# main_sch.net
KiCad netlist of a schematic drawn in Altium Designer
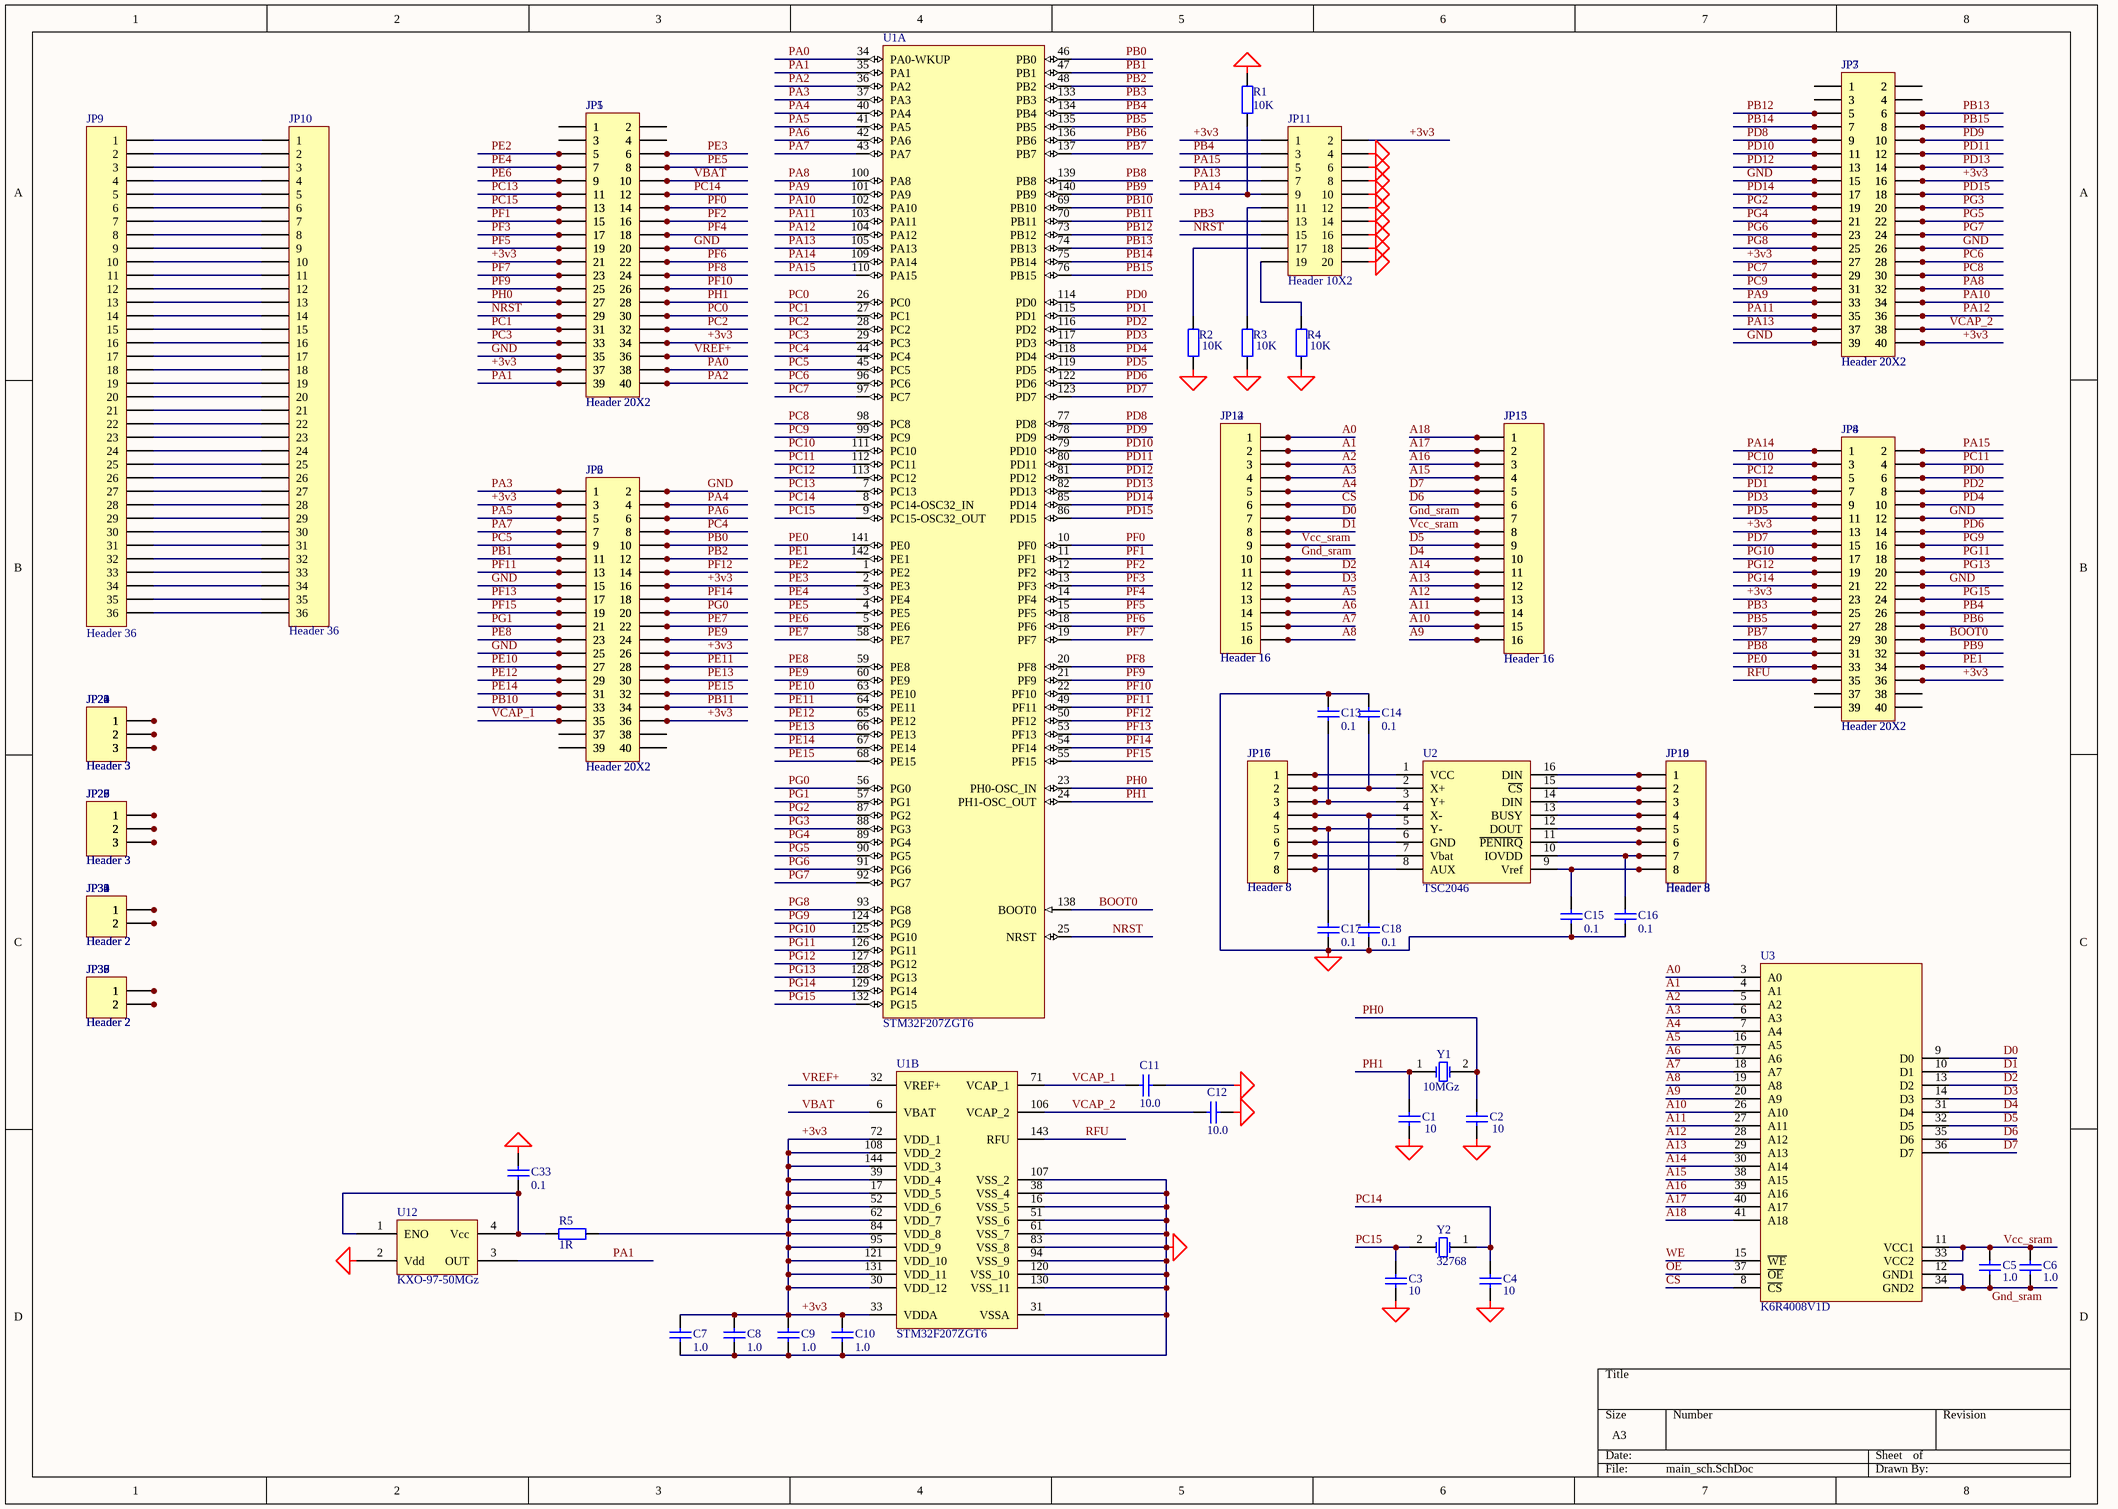
[diagram p0: main_sch.SchDoc]

(export (version "E")
  (design (tool "Eeschema 10.0.6"))
  (components
    (comp (ref "C1")
      (value "10")
      (footprint "_1206")
      (description "Capacitor")
      (fields (field (name "MANUFACTURER") "Generic Components") (field (name "PUBLISHER") "Altium Limited"))
      (libsource (lib "Miscellaneous Devices") (part "Cap Semi"))
    )
    (comp (ref "C2")
      (value "10")
      (footprint "_1206")
      (description "Capacitor")
      (fields (field (name "MANUFACTURER") "Generic Components") (field (name "PUBLISHER") "Altium Limited"))
      (libsource (lib "Miscellaneous Devices") (part "Cap Semi"))
    )
    (comp (ref "C3")
      (value "10")
      (footprint "_1206")
      (description "Capacitor")
      (fields (field (name "MANUFACTURER") "Generic Components") (field (name "PUBLISHER") "Altium Limited"))
      (libsource (lib "Miscellaneous Devices") (part "Cap Semi"))
    )
    (comp (ref "C4")
      (value "10")
      (footprint "_1206")
      (description "Capacitor")
      (fields (field (name "MANUFACTURER") "Generic Components") (field (name "PUBLISHER") "Altium Limited"))
      (libsource (lib "Miscellaneous Devices") (part "Cap Semi"))
    )
    (comp (ref "C5")
      (value "1.0")
      (footprint "_1206")
      (description "Capacitor")
      (fields (field (name "MANUFACTURER") "Generic Components") (field (name "PUBLISHER") "Altium Limited"))
      (libsource (lib "Miscellaneous Devices") (part "Cap Semi"))
    )
    (comp (ref "C6")
      (value "1.0")
      (footprint "_1206")
      (description "Capacitor")
      (fields (field (name "MANUFACTURER") "Generic Components") (field (name "PUBLISHER") "Altium Limited"))
      (libsource (lib "Miscellaneous Devices") (part "Cap Semi"))
    )
    (comp (ref "C7")
      (value "1.0")
      (footprint "_1206")
      (description "Capacitor")
      (fields (field (name "MANUFACTURER") "Generic Components") (field (name "PUBLISHER") "Altium Limited"))
      (libsource (lib "Miscellaneous Devices") (part "Cap Semi"))
    )
    (comp (ref "C8")
      (value "1.0")
      (footprint "_1206")
      (description "Capacitor")
      (fields (field (name "MANUFACTURER") "Generic Components") (field (name "PUBLISHER") "Altium Limited"))
      (libsource (lib "Miscellaneous Devices") (part "Cap Semi"))
    )
    (comp (ref "C9")
      (value "1.0")
      (footprint "_1206")
      (description "Capacitor")
      (fields (field (name "MANUFACTURER") "Generic Components") (field (name "PUBLISHER") "Altium Limited"))
      (libsource (lib "Miscellaneous Devices") (part "Cap Semi"))
    )
    (comp (ref "C10")
      (value "1.0")
      (footprint "_1206")
      (description "Capacitor")
      (fields (field (name "MANUFACTURER") "Generic Components") (field (name "PUBLISHER") "Altium Limited"))
      (libsource (lib "Miscellaneous Devices") (part "Cap Semi"))
    )
    (comp (ref "C11")
      (value "10.0")
      (footprint "_1206")
      (description "Capacitor")
      (fields (field (name "MANUFACTURER") "Generic Components") (field (name "PUBLISHER") "Altium Limited"))
      (libsource (lib "") (part "Cap Semi_1"))
    )
    (comp (ref "C12")
      (value "10.0")
      (footprint "_1206")
      (description "Capacitor")
      (fields (field (name "MANUFACTURER") "Generic Components") (field (name "PUBLISHER") "Altium Limited"))
      (libsource (lib "") (part "Cap Semi_1"))
    )
    (comp (ref "C13")
      (value "0.1")
      (footprint "_1206")
      (description "Capacitor")
      (fields (field (name "MANUFACTURER") "Generic Components") (field (name "PUBLISHER") "Altium Limited"))
      (libsource (lib "Miscellaneous Devices") (part "Cap Semi"))
    )
    (comp (ref "C14")
      (value "0.1")
      (footprint "_1206")
      (description "Capacitor")
      (fields (field (name "MANUFACTURER") "Generic Components") (field (name "PUBLISHER") "Altium Limited"))
      (libsource (lib "Miscellaneous Devices") (part "Cap Semi"))
    )
    (comp (ref "C15")
      (value "0.1")
      (footprint "_1206")
      (description "Capacitor")
      (fields (field (name "MANUFACTURER") "Generic Components") (field (name "PUBLISHER") "Altium Limited"))
      (libsource (lib "Miscellaneous Devices") (part "Cap Semi"))
    )
    (comp (ref "C16")
      (value "0.1")
      (footprint "_1206")
      (description "Capacitor")
      (fields (field (name "MANUFACTURER") "Generic Components") (field (name "PUBLISHER") "Altium Limited"))
      (libsource (lib "Miscellaneous Devices") (part "Cap Semi"))
    )
    (comp (ref "C17")
      (value "0.1")
      (footprint "_1206")
      (description "Capacitor")
      (fields (field (name "MANUFACTURER") "Generic Components") (field (name "PUBLISHER") "Altium Limited"))
      (libsource (lib "Miscellaneous Devices") (part "Cap Semi"))
    )
    (comp (ref "C18")
      (value "0.1")
      (footprint "_1206")
      (description "Capacitor")
      (fields (field (name "MANUFACTURER") "Generic Components") (field (name "PUBLISHER") "Altium Limited"))
      (libsource (lib "Miscellaneous Devices") (part "Cap Semi"))
    )
    (comp (ref "C33")
      (value "0.1")
      (footprint "_1206")
      (description "Capacitor (Semiconductor SIM Model)")
      (fields (field (name "MANUFACTURER") "Generic Components") (field (name "PUBLISHER") "Altium Limited"))
      (libsource (lib "Miscellaneous Devices") (part "Cap Semi"))
    )
    (comp (ref "JP1")
      (value "Header 20X2")
      (footprint "HDR2X20")
      (description "Header, 20-Pin, Dual row")
      (fields (field (name "MANUFACTURER") "Generic Components") (field (name "PUBLISHER") "Altium Limited"))
      (libsource (lib "Miscellaneous Connectors") (part "Header 20X2"))
    )
    (comp (ref "JP2")
      (value "Header 20X2")
      (footprint "HDR2X20")
      (description "Header, 20-Pin, Dual row")
      (fields (field (name "MANUFACTURER") "Generic Components") (field (name "PUBLISHER") "Altium Limited"))
      (libsource (lib "Miscellaneous Connectors") (part "Header 20X2"))
    )
    (comp (ref "JP3")
      (value "Header 20X2")
      (footprint "HDR2X20")
      (description "Header, 20-Pin, Dual row")
      (fields (field (name "MANUFACTURER") "Generic Components") (field (name "PUBLISHER") "Altium Limited"))
      (libsource (lib "Miscellaneous Connectors") (part "Header 20X2"))
    )
    (comp (ref "JP4")
      (value "Header 20X2")
      (footprint "HDR2X20")
      (description "Header, 20-Pin, Dual row")
      (fields (field (name "MANUFACTURER") "Generic Components") (field (name "PUBLISHER") "Altium Limited"))
      (libsource (lib "Miscellaneous Connectors") (part "Header 20X2"))
    )
    (comp (ref "JP5")
      (value "Header 20X2")
      (footprint "HDR2X20")
      (description "Header, 20-Pin, Dual row")
      (fields (field (name "MANUFACTURER") "Generic Components") (field (name "PUBLISHER") "Altium Limited"))
      (libsource (lib "Miscellaneous Connectors") (part "Header 20X2"))
    )
    (comp (ref "JP6")
      (value "Header 20X2")
      (footprint "HDR2X20")
      (description "Header, 20-Pin, Dual row")
      (fields (field (name "MANUFACTURER") "Generic Components") (field (name "PUBLISHER") "Altium Limited"))
      (libsource (lib "Miscellaneous Connectors") (part "Header 20X2"))
    )
    (comp (ref "JP7")
      (value "Header 20X2")
      (footprint "HDR2X20")
      (description "Header, 20-Pin, Dual row")
      (fields (field (name "MANUFACTURER") "Generic Components") (field (name "PUBLISHER") "Altium Limited"))
      (libsource (lib "Miscellaneous Connectors") (part "Header 20X2"))
    )
    (comp (ref "JP8")
      (value "Header 20X2")
      (footprint "HDR2X20")
      (description "Header, 20-Pin, Dual row")
      (fields (field (name "MANUFACTURER") "Generic Components") (field (name "PUBLISHER") "Altium Limited"))
      (libsource (lib "Miscellaneous Connectors") (part "Header 20X2"))
    )
    (comp (ref "JP9")
      (value "Header 36")
      (footprint "3-1734592-6")
      (description "Header, 36-Pin")
      (fields (field (name "MANUFACTURER") "Generic Components") (field (name "PUBLISHER") "Altium Limited"))
      (libsource (lib "") (part "Header 36_1"))
    )
    (comp (ref "JP10")
      (value "Header 36")
      (footprint "HDR2X18")
      (description "Header, 36-Pin")
      (fields (field (name "MANUFACTURER") "Generic Components") (field (name "PUBLISHER") "Altium Limited"))
      (libsource (lib "PAL") (part "Header 36"))
    )
    (comp (ref "JP11")
      (value "Header 10X2")
      (footprint "HDR2X10")
      (description "Header, 10-Pin, Dual row")
      (fields (field (name "MANUFACTURER") "Generic Components") (field (name "PUBLISHER") "Altium Limited"))
      (libsource (lib "Miscellaneous Connectors") (part "Header 10X2"))
    )
    (comp (ref "JP12")
      (value "Header 16")
      (footprint "HDR2X8")
      (description "Header, 16-Pin")
      (fields (field (name "MANUFACTURER") "Generic Components") (field (name "PUBLISHER") "Altium Limited"))
      (libsource (lib "") (part "Header 16_1"))
    )
    (comp (ref "JP13")
      (value "Header 16")
      (footprint "HDR2X8")
      (description "Header, 16-Pin")
      (fields (field (name "MANUFACTURER") "Generic Components") (field (name "PUBLISHER") "Altium Limited"))
      (libsource (lib "Miscellaneous Connectors") (part "Header 16"))
    )
    (comp (ref "JP14")
      (value "Header 16")
      (footprint "HDR2X8")
      (description "Header, 16-Pin")
      (fields (field (name "MANUFACTURER") "Generic Components") (field (name "PUBLISHER") "Altium Limited"))
      (libsource (lib "") (part "Header 16_1"))
    )
    (comp (ref "JP15")
      (value "Header 16")
      (footprint "HDR2X8")
      (description "Header, 16-Pin")
      (fields (field (name "MANUFACTURER") "Generic Components") (field (name "PUBLISHER") "Altium Limited"))
      (libsource (lib "Miscellaneous Connectors") (part "Header 16"))
    )
    (comp (ref "JP16")
      (value "Header 8")
      (footprint "HDR1X8")
      (description "Header, 8-Pin")
      (fields (field (name "MANUFACTURER") "Generic Components") (field (name "PUBLISHER") "Altium Limited"))
      (libsource (lib "") (part "Header 8_1"))
    )
    (comp (ref "JP17")
      (value "Header 8")
      (footprint "HDR1X8")
      (description "Header, 8-Pin")
      (fields (field (name "MANUFACTURER") "Generic Components") (field (name "PUBLISHER") "Altium Limited"))
      (libsource (lib "") (part "Header 8_1"))
    )
    (comp (ref "JP18")
      (value "Header 8")
      (footprint "HDR1X8")
      (description "Header, 8-Pin")
      (fields (field (name "MANUFACTURER") "Generic Components") (field (name "PUBLISHER") "Altium Limited"))
      (libsource (lib "Miscellaneous Connectors") (part "Header 8"))
    )
    (comp (ref "JP19")
      (value "Header 8")
      (footprint "HDR1X8")
      (description "Header, 8-Pin")
      (fields (field (name "MANUFACTURER") "Generic Components") (field (name "PUBLISHER") "Altium Limited"))
      (libsource (lib "Miscellaneous Connectors") (part "Header 8"))
    )
    (comp (ref "JP20")
      (value "Header 3")
      (footprint "HDR1X3")
      (description "Header, 3-Pin")
      (fields (field (name "MANUFACTURER") "Generic Components") (field (name "PUBLISHER") "Altium Limited"))
      (libsource (lib "Miscellaneous Connectors") (part "Header 3"))
    )
    (comp (ref "JP21")
      (value "Header 3")
      (footprint "HDR1X3")
      (description "Header, 3-Pin")
      (fields (field (name "MANUFACTURER") "Generic Components") (field (name "PUBLISHER") "Altium Limited"))
      (libsource (lib "Miscellaneous Connectors") (part "Header 3"))
    )
    (comp (ref "JP22")
      (value "Header 3")
      (footprint "HDR1X3")
      (description "Header, 3-Pin")
      (fields (field (name "MANUFACTURER") "Generic Components") (field (name "PUBLISHER") "Altium Limited"))
      (libsource (lib "Miscellaneous Connectors") (part "Header 3"))
    )
    (comp (ref "JP23")
      (value "Header 3")
      (footprint "HDR1X3")
      (description "Header, 3-Pin")
      (fields (field (name "MANUFACTURER") "Generic Components") (field (name "PUBLISHER") "Altium Limited"))
      (libsource (lib "Miscellaneous Connectors") (part "Header 3"))
    )
    (comp (ref "JP24")
      (value "Header 3")
      (footprint "HDR1X3")
      (description "Header, 3-Pin")
      (fields (field (name "MANUFACTURER") "Generic Components") (field (name "PUBLISHER") "Altium Limited"))
      (libsource (lib "Miscellaneous Connectors") (part "Header 3"))
    )
    (comp (ref "JP25")
      (value "Header 3")
      (footprint "HDR1X3")
      (description "Header, 3-Pin")
      (fields (field (name "MANUFACTURER") "Generic Components") (field (name "PUBLISHER") "Altium Limited"))
      (libsource (lib "Miscellaneous Connectors") (part "Header 3"))
    )
    (comp (ref "JP26")
      (value "Header 3")
      (footprint "HDR1X3")
      (description "Header, 3-Pin")
      (fields (field (name "MANUFACTURER") "Generic Components") (field (name "PUBLISHER") "Altium Limited"))
      (libsource (lib "Miscellaneous Connectors") (part "Header 3"))
    )
    (comp (ref "JP27")
      (value "Header 3")
      (footprint "HDR1X3")
      (description "Header, 3-Pin")
      (fields (field (name "MANUFACTURER") "Generic Components") (field (name "PUBLISHER") "Altium Limited"))
      (libsource (lib "Miscellaneous Connectors") (part "Header 3"))
    )
    (comp (ref "JP28")
      (value "Header 3")
      (footprint "HDR1X3")
      (description "Header, 3-Pin")
      (fields (field (name "MANUFACTURER") "Generic Components") (field (name "PUBLISHER") "Altium Limited"))
      (libsource (lib "Miscellaneous Connectors") (part "Header 3"))
    )
    (comp (ref "JP29")
      (value "Header 3")
      (footprint "HDR1X3")
      (description "Header, 3-Pin")
      (fields (field (name "MANUFACTURER") "Generic Components") (field (name "PUBLISHER") "Altium Limited"))
      (libsource (lib "Miscellaneous Connectors") (part "Header 3"))
    )
    (comp (ref "JP30")
      (value "Header 2")
      (footprint "HDR1X2")
      (description "Header, 2-Pin")
      (fields (field (name "MANUFACTURER") "Generic Components") (field (name "PUBLISHER") "Altium Limited"))
      (libsource (lib "Miscellaneous Connectors") (part "Header 2"))
    )
    (comp (ref "JP31")
      (value "Header 2")
      (footprint "HDR1X2")
      (description "Header, 2-Pin")
      (fields (field (name "MANUFACTURER") "Generic Components") (field (name "PUBLISHER") "Altium Limited"))
      (libsource (lib "Miscellaneous Connectors") (part "Header 2"))
    )
    (comp (ref "JP32")
      (value "Header 2")
      (footprint "HDR1X2")
      (description "Header, 2-Pin")
      (fields (field (name "MANUFACTURER") "Generic Components") (field (name "PUBLISHER") "Altium Limited"))
      (libsource (lib "Miscellaneous Connectors") (part "Header 2"))
    )
    (comp (ref "JP33")
      (value "Header 2")
      (footprint "HDR1X2")
      (description "Header, 2-Pin")
      (fields (field (name "MANUFACTURER") "Generic Components") (field (name "PUBLISHER") "Altium Limited"))
      (libsource (lib "Miscellaneous Connectors") (part "Header 2"))
    )
    (comp (ref "JP34")
      (value "Header 2")
      (footprint "HDR1X2")
      (description "Header, 2-Pin")
      (fields (field (name "MANUFACTURER") "Generic Components") (field (name "PUBLISHER") "Altium Limited"))
      (libsource (lib "Miscellaneous Connectors") (part "Header 2"))
    )
    (comp (ref "JP35")
      (value "Header 2")
      (footprint "HDR1X2")
      (description "Header, 2-Pin")
      (fields (field (name "MANUFACTURER") "Generic Components") (field (name "PUBLISHER") "Altium Limited"))
      (libsource (lib "Miscellaneous Connectors") (part "Header 2"))
    )
    (comp (ref "JP36")
      (value "Header 2")
      (footprint "HDR1X2")
      (description "Header, 2-Pin")
      (fields (field (name "MANUFACTURER") "Generic Components") (field (name "PUBLISHER") "Altium Limited"))
      (libsource (lib "Miscellaneous Connectors") (part "Header 2"))
    )
    (comp (ref "JP37")
      (value "Header 2")
      (footprint "HDR1X2")
      (description "Header, 2-Pin")
      (fields (field (name "MANUFACTURER") "Generic Components") (field (name "PUBLISHER") "Altium Limited"))
      (libsource (lib "Miscellaneous Connectors") (part "Header 2"))
    )
    (comp (ref "JP38")
      (value "Header 2")
      (footprint "HDR1X2")
      (description "Header, 2-Pin")
      (fields (field (name "MANUFACTURER") "Generic Components") (field (name "PUBLISHER") "Altium Limited"))
      (libsource (lib "Miscellaneous Connectors") (part "Header 2"))
    )
    (comp (ref "JP39")
      (value "Header 2")
      (footprint "HDR1X2")
      (description "Header, 2-Pin")
      (fields (field (name "MANUFACTURER") "Generic Components") (field (name "PUBLISHER") "Altium Limited"))
      (libsource (lib "Miscellaneous Connectors") (part "Header 2"))
    )
    (comp (ref "R1")
      (value "10K")
      (footprint "_1206")
      (description "Resistor")
      (fields (field (name "MANUFACTURER") "Generic Components") (field (name "PUBLISHER") "Altium Limited"))
      (libsource (lib "") (part "Res2_1"))
    )
    (comp (ref "R2")
      (value "10K")
      (footprint "_1206")
      (description "Resistor")
      (fields (field (name "MANUFACTURER") "Generic Components") (field (name "PUBLISHER") "Altium Limited"))
      (libsource (lib "Miscellaneous Devices") (part "Res2"))
    )
    (comp (ref "R3")
      (value "10K")
      (footprint "_1206")
      (description "Resistor")
      (fields (field (name "MANUFACTURER") "Generic Components") (field (name "PUBLISHER") "Altium Limited"))
      (libsource (lib "Miscellaneous Devices") (part "Res2"))
    )
    (comp (ref "R4")
      (value "10K")
      (footprint "_1206")
      (description "Resistor")
      (fields (field (name "MANUFACTURER") "Generic Components") (field (name "PUBLISHER") "Altium Limited"))
      (libsource (lib "Miscellaneous Devices") (part "Res2"))
    )
    (comp (ref "R5")
      (value "1R")
      (footprint "_1206")
      (description "Resistor")
      (fields (field (name "MANUFACTURER") "Generic Components") (field (name "PUBLISHER") "Altium Limited"))
      (libsource (lib "") (part "Res2_1"))
    )
    (comp (ref "U1")
      (value "STM32F207ZGT6")
      (footprint "F-QFP20X20-G144/N")
      (libsource (lib "STM32 F2") (part "STM32F207ZGT6"))
    )
    (comp (ref "U2") (value "TSC2046") (footprint "TSSO5X6-G16") (libsource (lib "PAL") (part "TSC2046")))
    (comp (ref "U3") (value "K6R4008V1D") (footprint "44-TSOP2") (libsource (lib "PAL") (part "K6R4008V1D")))
    (comp (ref "U12") (value "KXO-97-50MGz") (footprint "KXO-97") (libsource (lib "PAL") (part "KXO-97")))
    (comp (ref "Y1")
      (value "10MGz")
      (footprint "qwarz1")
      (description "Crystal Oscillator")
      (fields (field (name "MANUFACTURER") "Generic Components") (field (name "PUBLISHER") "Altium Limited"))
      (libsource (lib "Miscellaneous Devices") (part "XTAL"))
    )
    (comp (ref "Y2")
      (value "32768")
      (footprint "BCY-W2/D3.1")
      (description "Crystal Oscillator")
      (fields (field (name "MANUFACTURER") "Generic Components") (field (name "PUBLISHER") "Altium Limited"))
      (libsource (lib "Miscellaneous Devices") (part "XTAL"))
    )
  )
  (nets
    (net (code "1") (name "/+3v3") (class "Default")
      (node (ref "C10") (pin "1") (pinfunction "1_1") (pintype "passive"))
      (node (ref "C7") (pin "1") (pinfunction "1_1") (pintype "passive"))
      (node (ref "C8") (pin "1") (pinfunction "1_1") (pintype "passive"))
      (node (ref "C9") (pin "1") (pinfunction "1_1") (pintype "passive"))
      (node (ref "JP1") (pin "21") (pinfunction "21_21") (pintype "passive"))
      (node (ref "JP1") (pin "34") (pinfunction "34_34") (pintype "passive"))
      (node (ref "JP1") (pin "37") (pinfunction "37_37") (pintype "passive"))
      (node (ref "JP11") (pin "1") (pinfunction "1_1") (pintype "passive"))
      (node (ref "JP11") (pin "2") (pinfunction "2_2") (pintype "passive"))
      (node (ref "JP2") (pin "16") (pinfunction "16_16") (pintype "passive"))
      (node (ref "JP2") (pin "26") (pinfunction "26_26") (pintype "passive"))
      (node (ref "JP2") (pin "3") (pinfunction "3_3") (pintype "passive"))
      (node (ref "JP2") (pin "36") (pinfunction "36_36") (pintype "passive"))
      (node (ref "JP3") (pin "16") (pinfunction "16_16") (pintype "passive"))
      (node (ref "JP3") (pin "27") (pinfunction "27_27") (pintype "passive"))
      (node (ref "JP3") (pin "40") (pinfunction "40_40") (pintype "passive"))
      (node (ref "JP4") (pin "13") (pinfunction "13_13") (pintype "passive"))
      (node (ref "JP4") (pin "23") (pinfunction "23_23") (pintype "passive"))
      (node (ref "JP4") (pin "36") (pinfunction "36_36") (pintype "passive"))
      (node (ref "JP5") (pin "21") (pinfunction "21_21") (pintype "passive"))
      (node (ref "JP5") (pin "34") (pinfunction "34_34") (pintype "passive"))
      (node (ref "JP5") (pin "37") (pinfunction "37_37") (pintype "passive"))
      (node (ref "JP6") (pin "16") (pinfunction "16_16") (pintype "passive"))
      (node (ref "JP6") (pin "26") (pinfunction "26_26") (pintype "passive"))
      (node (ref "JP6") (pin "3") (pinfunction "3_3") (pintype "passive"))
      (node (ref "JP6") (pin "36") (pinfunction "36_36") (pintype "passive"))
      (node (ref "JP7") (pin "16") (pinfunction "16_16") (pintype "passive"))
      (node (ref "JP7") (pin "27") (pinfunction "27_27") (pintype "passive"))
      (node (ref "JP7") (pin "40") (pinfunction "40_40") (pintype "passive"))
      (node (ref "JP8") (pin "13") (pinfunction "13_13") (pintype "passive"))
      (node (ref "JP8") (pin "23") (pinfunction "23_23") (pintype "passive"))
      (node (ref "JP8") (pin "36") (pinfunction "36_36") (pintype "passive"))
      (node (ref "R5") (pin "2") (pinfunction "2_2") (pintype "passive"))
      (node (ref "U1") (pin "108") (pinfunction "VDD_2_108") (pintype "power_in"))
      (node (ref "U1") (pin "121") (pinfunction "VDD_10_121") (pintype "power_in"))
      (node (ref "U1") (pin "131") (pinfunction "VDD_11_131") (pintype "power_in"))
      (node (ref "U1") (pin "144") (pinfunction "VDD_3_144") (pintype "power_in"))
      (node (ref "U1") (pin "17") (pinfunction "VDD_5_17") (pintype "power_in"))
      (node (ref "U1") (pin "30") (pinfunction "VDD_12_30") (pintype "power_in"))
      (node (ref "U1") (pin "33") (pinfunction "VDDA_33") (pintype "power_in"))
      (node (ref "U1") (pin "39") (pinfunction "VDD_4_39") (pintype "power_in"))
      (node (ref "U1") (pin "52") (pinfunction "VDD_6_52") (pintype "power_in"))
      (node (ref "U1") (pin "62") (pinfunction "VDD_7_62") (pintype "power_in"))
      (node (ref "U1") (pin "72") (pinfunction "VDD_1_72") (pintype "power_in"))
      (node (ref "U1") (pin "84") (pinfunction "VDD_8_84") (pintype "power_in"))
      (node (ref "U1") (pin "95") (pinfunction "VDD_9_95") (pintype "power_in"))
    )
    (net (code "2") (name "/A0") (class "Default")
      (node (ref "JP12") (pin "1") (pinfunction "1_1") (pintype "passive"))
      (node (ref "JP14") (pin "1") (pinfunction "1_1") (pintype "passive"))
      (node (ref "U3") (pin "3") (pinfunction "A0_3") (pintype "passive"))
    )
    (net (code "3") (name "/A1") (class "Default")
      (node (ref "JP12") (pin "2") (pinfunction "2_2") (pintype "passive"))
      (node (ref "JP14") (pin "2") (pinfunction "2_2") (pintype "passive"))
      (node (ref "U3") (pin "4") (pinfunction "A1_4") (pintype "passive"))
    )
    (net (code "4") (name "/A2") (class "Default")
      (node (ref "JP12") (pin "3") (pinfunction "3_3") (pintype "passive"))
      (node (ref "JP14") (pin "3") (pinfunction "3_3") (pintype "passive"))
      (node (ref "U3") (pin "5") (pinfunction "A2_5") (pintype "passive"))
    )
    (net (code "5") (name "/A3") (class "Default")
      (node (ref "JP12") (pin "4") (pinfunction "4_4") (pintype "passive"))
      (node (ref "JP14") (pin "4") (pinfunction "4_4") (pintype "passive"))
      (node (ref "U3") (pin "6") (pinfunction "A3_6") (pintype "passive"))
    )
    (net (code "6") (name "/A4") (class "Default")
      (node (ref "JP12") (pin "5") (pinfunction "5_5") (pintype "passive"))
      (node (ref "JP14") (pin "5") (pinfunction "5_5") (pintype "passive"))
      (node (ref "U3") (pin "7") (pinfunction "A4_7") (pintype "passive"))
    )
    (net (code "7") (name "/A5") (class "Default")
      (node (ref "JP12") (pin "13") (pinfunction "13_13") (pintype "passive"))
      (node (ref "JP14") (pin "13") (pinfunction "13_13") (pintype "passive"))
      (node (ref "U3") (pin "16") (pinfunction "A5_16") (pintype "passive"))
    )
    (net (code "8") (name "/A6") (class "Default")
      (node (ref "JP12") (pin "14") (pinfunction "14_14") (pintype "passive"))
      (node (ref "JP14") (pin "14") (pinfunction "14_14") (pintype "passive"))
      (node (ref "U3") (pin "17") (pinfunction "A6_17") (pintype "passive"))
    )
    (net (code "9") (name "/A7") (class "Default")
      (node (ref "JP12") (pin "15") (pinfunction "15_15") (pintype "passive"))
      (node (ref "JP14") (pin "15") (pinfunction "15_15") (pintype "passive"))
      (node (ref "U3") (pin "18") (pinfunction "A7_18") (pintype "passive"))
    )
    (net (code "10") (name "/A8") (class "Default")
      (node (ref "JP12") (pin "16") (pinfunction "16_16") (pintype "passive"))
      (node (ref "JP14") (pin "16") (pinfunction "16_16") (pintype "passive"))
      (node (ref "U3") (pin "19") (pinfunction "A8_19") (pintype "passive"))
    )
    (net (code "11") (name "/A9") (class "Default")
      (node (ref "JP13") (pin "16") (pinfunction "16_16") (pintype "passive"))
      (node (ref "JP15") (pin "16") (pinfunction "16_16") (pintype "passive"))
      (node (ref "U3") (pin "20") (pinfunction "A9_20") (pintype "passive"))
    )
    (net (code "12") (name "/A10") (class "Default")
      (node (ref "JP13") (pin "15") (pinfunction "15_15") (pintype "passive"))
      (node (ref "JP15") (pin "15") (pinfunction "15_15") (pintype "passive"))
      (node (ref "U3") (pin "26") (pinfunction "A10_26") (pintype "passive"))
    )
    (net (code "13") (name "/A11") (class "Default")
      (node (ref "JP13") (pin "14") (pinfunction "14_14") (pintype "passive"))
      (node (ref "JP15") (pin "14") (pinfunction "14_14") (pintype "passive"))
      (node (ref "U3") (pin "27") (pinfunction "A11_27") (pintype "passive"))
    )
    (net (code "14") (name "/A12") (class "Default")
      (node (ref "JP13") (pin "13") (pinfunction "13_13") (pintype "passive"))
      (node (ref "JP15") (pin "13") (pinfunction "13_13") (pintype "passive"))
      (node (ref "U3") (pin "28") (pinfunction "A12_28") (pintype "passive"))
    )
    (net (code "15") (name "/A13") (class "Default")
      (node (ref "JP13") (pin "12") (pinfunction "12_12") (pintype "passive"))
      (node (ref "JP15") (pin "12") (pinfunction "12_12") (pintype "passive"))
      (node (ref "U3") (pin "29") (pinfunction "A13_29") (pintype "passive"))
    )
    (net (code "16") (name "/A14") (class "Default")
      (node (ref "JP13") (pin "11") (pinfunction "11_11") (pintype "passive"))
      (node (ref "JP15") (pin "11") (pinfunction "11_11") (pintype "passive"))
      (node (ref "U3") (pin "30") (pinfunction "A14_30") (pintype "passive"))
    )
    (net (code "17") (name "/A15") (class "Default")
      (node (ref "JP13") (pin "4") (pinfunction "4_4") (pintype "passive"))
      (node (ref "JP15") (pin "4") (pinfunction "4_4") (pintype "passive"))
      (node (ref "U3") (pin "38") (pinfunction "A15_38") (pintype "passive"))
    )
    (net (code "18") (name "/A16") (class "Default")
      (node (ref "JP13") (pin "3") (pinfunction "3_3") (pintype "passive"))
      (node (ref "JP15") (pin "3") (pinfunction "3_3") (pintype "passive"))
      (node (ref "U3") (pin "39") (pinfunction "A16_39") (pintype "passive"))
    )
    (net (code "19") (name "/A17") (class "Default")
      (node (ref "JP13") (pin "2") (pinfunction "2_2") (pintype "passive"))
      (node (ref "JP15") (pin "2") (pinfunction "2_2") (pintype "passive"))
      (node (ref "U3") (pin "40") (pinfunction "A17_40") (pintype "passive"))
    )
    (net (code "20") (name "/A18") (class "Default")
      (node (ref "JP13") (pin "1") (pinfunction "1_1") (pintype "passive"))
      (node (ref "JP15") (pin "1") (pinfunction "1_1") (pintype "passive"))
      (node (ref "U3") (pin "41") (pinfunction "A18_41") (pintype "passive"))
    )
    (net (code "21") (name "/BOOT0") (class "Default")
      (node (ref "JP4") (pin "30") (pinfunction "30_30") (pintype "passive"))
      (node (ref "JP8") (pin "30") (pinfunction "30_30") (pintype "passive"))
      (node (ref "U1") (pin "138") (pinfunction "BOOT0_138") (pintype "input"))
    )
    (net (code "22") (name "/CS") (class "Default")
      (node (ref "JP12") (pin "6") (pinfunction "6_6") (pintype "passive"))
      (node (ref "JP14") (pin "6") (pinfunction "6_6") (pintype "passive"))
      (node (ref "U3") (pin "8") (pinfunction "~{CS}_8") (pintype "passive"))
    )
    (net (code "23") (name "/D0") (class "Default")
      (node (ref "JP12") (pin "7") (pinfunction "7_7") (pintype "passive"))
      (node (ref "JP14") (pin "7") (pinfunction "7_7") (pintype "passive"))
      (node (ref "U3") (pin "9") (pinfunction "D0_9") (pintype "passive"))
    )
    (net (code "24") (name "/D1") (class "Default")
      (node (ref "JP12") (pin "8") (pinfunction "8_8") (pintype "passive"))
      (node (ref "JP14") (pin "8") (pinfunction "8_8") (pintype "passive"))
      (node (ref "U3") (pin "10") (pinfunction "D1_10") (pintype "passive"))
    )
    (net (code "25") (name "/D2") (class "Default")
      (node (ref "JP12") (pin "11") (pinfunction "11_11") (pintype "passive"))
      (node (ref "JP14") (pin "11") (pinfunction "11_11") (pintype "passive"))
      (node (ref "U3") (pin "13") (pinfunction "D2_13") (pintype "passive"))
    )
    (net (code "26") (name "/D3") (class "Default")
      (node (ref "JP12") (pin "12") (pinfunction "12_12") (pintype "passive"))
      (node (ref "JP14") (pin "12") (pinfunction "12_12") (pintype "passive"))
      (node (ref "U3") (pin "14") (pinfunction "D3_14") (pintype "passive"))
    )
    (net (code "27") (name "/D4") (class "Default")
      (node (ref "JP13") (pin "10") (pinfunction "10_10") (pintype "passive"))
      (node (ref "JP15") (pin "10") (pinfunction "10_10") (pintype "passive"))
      (node (ref "U3") (pin "31") (pinfunction "D4_31") (pintype "passive"))
    )
    (net (code "28") (name "/D5") (class "Default")
      (node (ref "JP13") (pin "9") (pinfunction "9_9") (pintype "passive"))
      (node (ref "JP15") (pin "9") (pinfunction "9_9") (pintype "passive"))
      (node (ref "U3") (pin "32") (pinfunction "D5_32") (pintype "passive"))
    )
    (net (code "29") (name "/D6") (class "Default")
      (node (ref "JP13") (pin "6") (pinfunction "6_6") (pintype "passive"))
      (node (ref "JP15") (pin "6") (pinfunction "6_6") (pintype "passive"))
      (node (ref "U3") (pin "35") (pinfunction "D6_35") (pintype "passive"))
    )
    (net (code "30") (name "/D7") (class "Default")
      (node (ref "JP13") (pin "5") (pinfunction "5_5") (pintype "passive"))
      (node (ref "JP15") (pin "5") (pinfunction "5_5") (pintype "passive"))
      (node (ref "U3") (pin "36") (pinfunction "D7_36") (pintype "passive"))
    )
    (net (code "31") (name "/Gnd_sram") (class "Default")
      (node (ref "C5") (pin "1") (pinfunction "1_1") (pintype "passive"))
      (node (ref "C6") (pin "1") (pinfunction "1_1") (pintype "passive"))
      (node (ref "JP12") (pin "10") (pinfunction "10_10") (pintype "passive"))
      (node (ref "JP13") (pin "7") (pinfunction "7_7") (pintype "passive"))
      (node (ref "JP14") (pin "10") (pinfunction "10_10") (pintype "passive"))
      (node (ref "JP15") (pin "7") (pinfunction "7_7") (pintype "passive"))
      (node (ref "U3") (pin "12") (pinfunction "GND1_12") (pintype "passive"))
      (node (ref "U3") (pin "34") (pinfunction "GND2_34") (pintype "passive"))
    )
    (net (code "32") (name "/NRST") (class "Default")
      (node (ref "JP1") (pin "29") (pinfunction "29_29") (pintype "passive"))
      (node (ref "JP11") (pin "15") (pinfunction "15_15") (pintype "passive"))
      (node (ref "JP5") (pin "29") (pinfunction "29_29") (pintype "passive"))
      (node (ref "U1") (pin "25") (pinfunction "NRST_25") (pintype "bidirectional"))
    )
    (net (code "33") (name "/OE") (class "Default")
      (node (ref "U3") (pin "37") (pinfunction "~{OE}_37") (pintype "passive"))
    )
    (net (code "34") (name "/PA0") (class "Default")
      (node (ref "JP1") (pin "38") (pinfunction "38_38") (pintype "passive"))
      (node (ref "JP5") (pin "38") (pinfunction "38_38") (pintype "passive"))
      (node (ref "U1") (pin "34") (pinfunction "PA0-WKUP_34") (pintype "bidirectional"))
    )
    (net (code "35") (name "/PA1") (class "Default")
      (node (ref "JP1") (pin "39") (pinfunction "39_39") (pintype "passive"))
      (node (ref "JP5") (pin "39") (pinfunction "39_39") (pintype "passive"))
      (node (ref "U1") (pin "35") (pinfunction "PA1_35") (pintype "bidirectional"))
      (node (ref "U12") (pin "3") (pinfunction "OUT_3") (pintype "passive"))
    )
    (net (code "36") (name "/PA2") (class "Default")
      (node (ref "JP1") (pin "40") (pinfunction "40_40") (pintype "passive"))
      (node (ref "JP5") (pin "40") (pinfunction "40_40") (pintype "passive"))
      (node (ref "U1") (pin "36") (pinfunction "PA2_36") (pintype "bidirectional"))
    )
    (net (code "37") (name "/PA3") (class "Default")
      (node (ref "JP2") (pin "1") (pinfunction "1_1") (pintype "passive"))
      (node (ref "JP6") (pin "1") (pinfunction "1_1") (pintype "passive"))
      (node (ref "U1") (pin "37") (pinfunction "PA3_37") (pintype "bidirectional"))
    )
    (net (code "38") (name "/PA4") (class "Default")
      (node (ref "JP2") (pin "4") (pinfunction "4_4") (pintype "passive"))
      (node (ref "JP6") (pin "4") (pinfunction "4_4") (pintype "passive"))
      (node (ref "U1") (pin "40") (pinfunction "PA4_40") (pintype "bidirectional"))
    )
    (net (code "39") (name "/PA5") (class "Default")
      (node (ref "JP2") (pin "5") (pinfunction "5_5") (pintype "passive"))
      (node (ref "JP6") (pin "5") (pinfunction "5_5") (pintype "passive"))
      (node (ref "U1") (pin "41") (pinfunction "PA5_41") (pintype "bidirectional"))
    )
    (net (code "40") (name "/PA6") (class "Default")
      (node (ref "JP2") (pin "6") (pinfunction "6_6") (pintype "passive"))
      (node (ref "JP6") (pin "6") (pinfunction "6_6") (pintype "passive"))
      (node (ref "U1") (pin "42") (pinfunction "PA6_42") (pintype "bidirectional"))
    )
    (net (code "41") (name "/PA7") (class "Default")
      (node (ref "JP2") (pin "7") (pinfunction "7_7") (pintype "passive"))
      (node (ref "JP6") (pin "7") (pinfunction "7_7") (pintype "passive"))
      (node (ref "U1") (pin "43") (pinfunction "PA7_43") (pintype "bidirectional"))
    )
    (net (code "42") (name "/PA8") (class "Default")
      (node (ref "JP3") (pin "32") (pinfunction "32_32") (pintype "passive"))
      (node (ref "JP7") (pin "32") (pinfunction "32_32") (pintype "passive"))
      (node (ref "U1") (pin "100") (pinfunction "PA8_100") (pintype "bidirectional"))
    )
    (net (code "43") (name "/PA9") (class "Default")
      (node (ref "JP3") (pin "33") (pinfunction "33_33") (pintype "passive"))
      (node (ref "JP7") (pin "33") (pinfunction "33_33") (pintype "passive"))
      (node (ref "U1") (pin "101") (pinfunction "PA9_101") (pintype "bidirectional"))
    )
    (net (code "44") (name "/PA10") (class "Default")
      (node (ref "JP3") (pin "34") (pinfunction "34_34") (pintype "passive"))
      (node (ref "JP7") (pin "34") (pinfunction "34_34") (pintype "passive"))
      (node (ref "U1") (pin "102") (pinfunction "PA10_102") (pintype "bidirectional"))
    )
    (net (code "45") (name "/PA11") (class "Default")
      (node (ref "JP3") (pin "35") (pinfunction "35_35") (pintype "passive"))
      (node (ref "JP7") (pin "35") (pinfunction "35_35") (pintype "passive"))
      (node (ref "U1") (pin "103") (pinfunction "PA11_103") (pintype "bidirectional"))
    )
    (net (code "46") (name "/PA12") (class "Default")
      (node (ref "JP3") (pin "36") (pinfunction "36_36") (pintype "passive"))
      (node (ref "JP7") (pin "36") (pinfunction "36_36") (pintype "passive"))
      (node (ref "U1") (pin "104") (pinfunction "PA12_104") (pintype "bidirectional"))
    )
    (net (code "47") (name "/PA13") (class "Default")
      (node (ref "JP11") (pin "7") (pinfunction "7_7") (pintype "passive"))
      (node (ref "JP3") (pin "37") (pinfunction "37_37") (pintype "passive"))
      (node (ref "JP7") (pin "37") (pinfunction "37_37") (pintype "passive"))
      (node (ref "U1") (pin "105") (pinfunction "PA13_105") (pintype "bidirectional"))
    )
    (net (code "48") (name "/PA14") (class "Default")
      (node (ref "JP11") (pin "9") (pinfunction "9_9") (pintype "passive"))
      (node (ref "JP4") (pin "1") (pinfunction "1_1") (pintype "passive"))
      (node (ref "JP8") (pin "1") (pinfunction "1_1") (pintype "passive"))
      (node (ref "R1") (pin "1") (pinfunction "1_1") (pintype "passive"))
      (node (ref "U1") (pin "109") (pinfunction "PA14_109") (pintype "bidirectional"))
    )
    (net (code "49") (name "/PA15") (class "Default")
      (node (ref "JP11") (pin "5") (pinfunction "5_5") (pintype "passive"))
      (node (ref "JP4") (pin "2") (pinfunction "2_2") (pintype "passive"))
      (node (ref "JP8") (pin "2") (pinfunction "2_2") (pintype "passive"))
      (node (ref "U1") (pin "110") (pinfunction "PA15_110") (pintype "bidirectional"))
    )
    (net (code "50") (name "/PB0") (class "Default")
      (node (ref "JP2") (pin "10") (pinfunction "10_10") (pintype "passive"))
      (node (ref "JP6") (pin "10") (pinfunction "10_10") (pintype "passive"))
      (node (ref "U1") (pin "46") (pinfunction "PB0_46") (pintype "bidirectional"))
    )
    (net (code "51") (name "/PB1") (class "Default")
      (node (ref "JP2") (pin "11") (pinfunction "11_11") (pintype "passive"))
      (node (ref "JP6") (pin "11") (pinfunction "11_11") (pintype "passive"))
      (node (ref "U1") (pin "47") (pinfunction "PB1_47") (pintype "bidirectional"))
    )
    (net (code "52") (name "/PB2") (class "Default")
      (node (ref "JP2") (pin "12") (pinfunction "12_12") (pintype "passive"))
      (node (ref "JP6") (pin "12") (pinfunction "12_12") (pintype "passive"))
      (node (ref "U1") (pin "48") (pinfunction "PB2_48") (pintype "bidirectional"))
    )
    (net (code "53") (name "/PB3") (class "Default")
      (node (ref "JP11") (pin "13") (pinfunction "13_13") (pintype "passive"))
      (node (ref "JP4") (pin "25") (pinfunction "25_25") (pintype "passive"))
      (node (ref "JP8") (pin "25") (pinfunction "25_25") (pintype "passive"))
      (node (ref "U1") (pin "133") (pinfunction "PB3_133") (pintype "bidirectional"))
    )
    (net (code "54") (name "/PB4") (class "Default")
      (node (ref "JP11") (pin "3") (pinfunction "3_3") (pintype "passive"))
      (node (ref "JP4") (pin "26") (pinfunction "26_26") (pintype "passive"))
      (node (ref "JP8") (pin "26") (pinfunction "26_26") (pintype "passive"))
      (node (ref "U1") (pin "134") (pinfunction "PB4_134") (pintype "bidirectional"))
    )
    (net (code "55") (name "/PB5") (class "Default")
      (node (ref "JP4") (pin "27") (pinfunction "27_27") (pintype "passive"))
      (node (ref "JP8") (pin "27") (pinfunction "27_27") (pintype "passive"))
      (node (ref "U1") (pin "135") (pinfunction "PB5_135") (pintype "bidirectional"))
    )
    (net (code "56") (name "/PB6") (class "Default")
      (node (ref "JP4") (pin "28") (pinfunction "28_28") (pintype "passive"))
      (node (ref "JP8") (pin "28") (pinfunction "28_28") (pintype "passive"))
      (node (ref "U1") (pin "136") (pinfunction "PB6_136") (pintype "bidirectional"))
    )
    (net (code "57") (name "/PB7") (class "Default")
      (node (ref "JP4") (pin "29") (pinfunction "29_29") (pintype "passive"))
      (node (ref "JP8") (pin "29") (pinfunction "29_29") (pintype "passive"))
      (node (ref "U1") (pin "137") (pinfunction "PB7_137") (pintype "bidirectional"))
    )
    (net (code "58") (name "/PB8") (class "Default")
      (node (ref "JP4") (pin "31") (pinfunction "31_31") (pintype "passive"))
      (node (ref "JP8") (pin "31") (pinfunction "31_31") (pintype "passive"))
      (node (ref "U1") (pin "139") (pinfunction "PB8_139") (pintype "bidirectional"))
    )
    (net (code "59") (name "/PB9") (class "Default")
      (node (ref "JP4") (pin "32") (pinfunction "32_32") (pintype "passive"))
      (node (ref "JP8") (pin "32") (pinfunction "32_32") (pintype "passive"))
      (node (ref "U1") (pin "140") (pinfunction "PB9_140") (pintype "bidirectional"))
    )
    (net (code "60") (name "/PB10") (class "Default")
      (node (ref "JP2") (pin "33") (pinfunction "33_33") (pintype "passive"))
      (node (ref "JP6") (pin "33") (pinfunction "33_33") (pintype "passive"))
      (node (ref "U1") (pin "69") (pinfunction "PB10_69") (pintype "bidirectional"))
    )
    (net (code "61") (name "/PB11") (class "Default")
      (node (ref "JP2") (pin "34") (pinfunction "34_34") (pintype "passive"))
      (node (ref "JP6") (pin "34") (pinfunction "34_34") (pintype "passive"))
      (node (ref "U1") (pin "70") (pinfunction "PB11_70") (pintype "bidirectional"))
    )
    (net (code "62") (name "/PB12") (class "Default")
      (node (ref "JP3") (pin "5") (pinfunction "5_5") (pintype "passive"))
      (node (ref "JP7") (pin "5") (pinfunction "5_5") (pintype "passive"))
      (node (ref "U1") (pin "73") (pinfunction "PB12_73") (pintype "bidirectional"))
    )
    (net (code "63") (name "/PB13") (class "Default")
      (node (ref "JP3") (pin "6") (pinfunction "6_6") (pintype "passive"))
      (node (ref "JP7") (pin "6") (pinfunction "6_6") (pintype "passive"))
      (node (ref "U1") (pin "74") (pinfunction "PB13_74") (pintype "bidirectional"))
    )
    (net (code "64") (name "/PB14") (class "Default")
      (node (ref "JP3") (pin "7") (pinfunction "7_7") (pintype "passive"))
      (node (ref "JP7") (pin "7") (pinfunction "7_7") (pintype "passive"))
      (node (ref "U1") (pin "75") (pinfunction "PB14_75") (pintype "bidirectional"))
    )
    (net (code "65") (name "/PB15") (class "Default")
      (node (ref "JP3") (pin "8") (pinfunction "8_8") (pintype "passive"))
      (node (ref "JP7") (pin "8") (pinfunction "8_8") (pintype "passive"))
      (node (ref "U1") (pin "76") (pinfunction "PB15_76") (pintype "bidirectional"))
    )
    (net (code "66") (name "/PC0") (class "Default")
      (node (ref "JP1") (pin "30") (pinfunction "30_30") (pintype "passive"))
      (node (ref "JP5") (pin "30") (pinfunction "30_30") (pintype "passive"))
      (node (ref "U1") (pin "26") (pinfunction "PC0_26") (pintype "bidirectional"))
    )
    (net (code "67") (name "/PC1") (class "Default")
      (node (ref "JP1") (pin "31") (pinfunction "31_31") (pintype "passive"))
      (node (ref "JP5") (pin "31") (pinfunction "31_31") (pintype "passive"))
      (node (ref "U1") (pin "27") (pinfunction "PC1_27") (pintype "bidirectional"))
    )
    (net (code "68") (name "/PC2") (class "Default")
      (node (ref "JP1") (pin "32") (pinfunction "32_32") (pintype "passive"))
      (node (ref "JP5") (pin "32") (pinfunction "32_32") (pintype "passive"))
      (node (ref "U1") (pin "28") (pinfunction "PC2_28") (pintype "bidirectional"))
    )
    (net (code "69") (name "/PC3") (class "Default")
      (node (ref "JP1") (pin "33") (pinfunction "33_33") (pintype "passive"))
      (node (ref "JP5") (pin "33") (pinfunction "33_33") (pintype "passive"))
      (node (ref "U1") (pin "29") (pinfunction "PC3_29") (pintype "bidirectional"))
    )
    (net (code "70") (name "/PC4") (class "Default")
      (node (ref "JP2") (pin "8") (pinfunction "8_8") (pintype "passive"))
      (node (ref "JP6") (pin "8") (pinfunction "8_8") (pintype "passive"))
      (node (ref "U1") (pin "44") (pinfunction "PC4_44") (pintype "bidirectional"))
    )
    (net (code "71") (name "/PC5") (class "Default")
      (node (ref "JP2") (pin "9") (pinfunction "9_9") (pintype "passive"))
      (node (ref "JP6") (pin "9") (pinfunction "9_9") (pintype "passive"))
      (node (ref "U1") (pin "45") (pinfunction "PC5_45") (pintype "bidirectional"))
    )
    (net (code "72") (name "/PC6") (class "Default")
      (node (ref "JP3") (pin "28") (pinfunction "28_28") (pintype "passive"))
      (node (ref "JP7") (pin "28") (pinfunction "28_28") (pintype "passive"))
      (node (ref "U1") (pin "96") (pinfunction "PC6_96") (pintype "bidirectional"))
    )
    (net (code "73") (name "/PC7") (class "Default")
      (node (ref "JP3") (pin "29") (pinfunction "29_29") (pintype "passive"))
      (node (ref "JP7") (pin "29") (pinfunction "29_29") (pintype "passive"))
      (node (ref "U1") (pin "97") (pinfunction "PC7_97") (pintype "bidirectional"))
    )
    (net (code "74") (name "/PC8") (class "Default")
      (node (ref "JP3") (pin "30") (pinfunction "30_30") (pintype "passive"))
      (node (ref "JP7") (pin "30") (pinfunction "30_30") (pintype "passive"))
      (node (ref "U1") (pin "98") (pinfunction "PC8_98") (pintype "bidirectional"))
    )
    (net (code "75") (name "/PC9") (class "Default")
      (node (ref "JP3") (pin "31") (pinfunction "31_31") (pintype "passive"))
      (node (ref "JP7") (pin "31") (pinfunction "31_31") (pintype "passive"))
      (node (ref "U1") (pin "99") (pinfunction "PC9_99") (pintype "bidirectional"))
    )
    (net (code "76") (name "/PC10") (class "Default")
      (node (ref "JP4") (pin "3") (pinfunction "3_3") (pintype "passive"))
      (node (ref "JP8") (pin "3") (pinfunction "3_3") (pintype "passive"))
      (node (ref "U1") (pin "111") (pinfunction "PC10_111") (pintype "bidirectional"))
    )
    (net (code "77") (name "/PC11") (class "Default")
      (node (ref "JP4") (pin "4") (pinfunction "4_4") (pintype "passive"))
      (node (ref "JP8") (pin "4") (pinfunction "4_4") (pintype "passive"))
      (node (ref "U1") (pin "112") (pinfunction "PC11_112") (pintype "bidirectional"))
    )
    (net (code "78") (name "/PC12") (class "Default")
      (node (ref "JP4") (pin "5") (pinfunction "5_5") (pintype "passive"))
      (node (ref "JP8") (pin "5") (pinfunction "5_5") (pintype "passive"))
      (node (ref "U1") (pin "113") (pinfunction "PC12_113") (pintype "bidirectional"))
    )
    (net (code "79") (name "/PC13") (class "Default")
      (node (ref "JP1") (pin "11") (pinfunction "11_11") (pintype "passive"))
      (node (ref "JP5") (pin "11") (pinfunction "11_11") (pintype "passive"))
      (node (ref "U1") (pin "7") (pinfunction "PC13_7") (pintype "bidirectional"))
    )
    (net (code "80") (name "/PC14") (class "Default")
      (node (ref "C4") (pin "2") (pinfunction "2_2") (pintype "passive"))
      (node (ref "JP1") (pin "12") (pinfunction "12_12") (pintype "passive"))
      (node (ref "JP5") (pin "12") (pinfunction "12_12") (pintype "passive"))
      (node (ref "U1") (pin "8") (pinfunction "PC14-OSC32_IN_8") (pintype "bidirectional"))
      (node (ref "Y2") (pin "1") (pinfunction "OSC1_1") (pintype "passive"))
    )
    (net (code "81") (name "/PC15") (class "Default")
      (node (ref "C3") (pin "2") (pinfunction "2_2") (pintype "passive"))
      (node (ref "JP1") (pin "13") (pinfunction "13_13") (pintype "passive"))
      (node (ref "JP5") (pin "13") (pinfunction "13_13") (pintype "passive"))
      (node (ref "U1") (pin "9") (pinfunction "PC15-OSC32_OUT_9") (pintype "bidirectional"))
      (node (ref "Y2") (pin "2") (pinfunction "OSC2_2") (pintype "passive"))
    )
    (net (code "82") (name "/PD0") (class "Default")
      (node (ref "JP4") (pin "6") (pinfunction "6_6") (pintype "passive"))
      (node (ref "JP8") (pin "6") (pinfunction "6_6") (pintype "passive"))
      (node (ref "U1") (pin "114") (pinfunction "PD0_114") (pintype "bidirectional"))
    )
    (net (code "83") (name "/PD1") (class "Default")
      (node (ref "JP4") (pin "7") (pinfunction "7_7") (pintype "passive"))
      (node (ref "JP8") (pin "7") (pinfunction "7_7") (pintype "passive"))
      (node (ref "U1") (pin "115") (pinfunction "PD1_115") (pintype "bidirectional"))
    )
    (net (code "84") (name "/PD2") (class "Default")
      (node (ref "JP4") (pin "8") (pinfunction "8_8") (pintype "passive"))
      (node (ref "JP8") (pin "8") (pinfunction "8_8") (pintype "passive"))
      (node (ref "U1") (pin "116") (pinfunction "PD2_116") (pintype "bidirectional"))
    )
    (net (code "85") (name "/PD3") (class "Default")
      (node (ref "JP4") (pin "9") (pinfunction "9_9") (pintype "passive"))
      (node (ref "JP8") (pin "9") (pinfunction "9_9") (pintype "passive"))
      (node (ref "U1") (pin "117") (pinfunction "PD3_117") (pintype "bidirectional"))
    )
    (net (code "86") (name "/PD4") (class "Default")
      (node (ref "JP4") (pin "10") (pinfunction "10_10") (pintype "passive"))
      (node (ref "JP8") (pin "10") (pinfunction "10_10") (pintype "passive"))
      (node (ref "U1") (pin "118") (pinfunction "PD4_118") (pintype "bidirectional"))
    )
    (net (code "87") (name "/PD5") (class "Default")
      (node (ref "JP4") (pin "11") (pinfunction "11_11") (pintype "passive"))
      (node (ref "JP8") (pin "11") (pinfunction "11_11") (pintype "passive"))
      (node (ref "U1") (pin "119") (pinfunction "PD5_119") (pintype "bidirectional"))
    )
    (net (code "88") (name "/PD6") (class "Default")
      (node (ref "JP4") (pin "14") (pinfunction "14_14") (pintype "passive"))
      (node (ref "JP8") (pin "14") (pinfunction "14_14") (pintype "passive"))
      (node (ref "U1") (pin "122") (pinfunction "PD6_122") (pintype "bidirectional"))
    )
    (net (code "89") (name "/PD7") (class "Default")
      (node (ref "JP4") (pin "15") (pinfunction "15_15") (pintype "passive"))
      (node (ref "JP8") (pin "15") (pinfunction "15_15") (pintype "passive"))
      (node (ref "U1") (pin "123") (pinfunction "PD7_123") (pintype "bidirectional"))
    )
    (net (code "90") (name "/PD8") (class "Default")
      (node (ref "JP3") (pin "9") (pinfunction "9_9") (pintype "passive"))
      (node (ref "JP7") (pin "9") (pinfunction "9_9") (pintype "passive"))
      (node (ref "U1") (pin "77") (pinfunction "PD8_77") (pintype "bidirectional"))
    )
    (net (code "91") (name "/PD9") (class "Default")
      (node (ref "JP3") (pin "10") (pinfunction "10_10") (pintype "passive"))
      (node (ref "JP7") (pin "10") (pinfunction "10_10") (pintype "passive"))
      (node (ref "U1") (pin "78") (pinfunction "PD9_78") (pintype "bidirectional"))
    )
    (net (code "92") (name "/PD10") (class "Default")
      (node (ref "JP3") (pin "11") (pinfunction "11_11") (pintype "passive"))
      (node (ref "JP7") (pin "11") (pinfunction "11_11") (pintype "passive"))
      (node (ref "U1") (pin "79") (pinfunction "PD10_79") (pintype "bidirectional"))
    )
    (net (code "93") (name "/PD11") (class "Default")
      (node (ref "JP3") (pin "12") (pinfunction "12_12") (pintype "passive"))
      (node (ref "JP7") (pin "12") (pinfunction "12_12") (pintype "passive"))
      (node (ref "U1") (pin "80") (pinfunction "PD11_80") (pintype "bidirectional"))
    )
    (net (code "94") (name "/PD12") (class "Default")
      (node (ref "JP3") (pin "13") (pinfunction "13_13") (pintype "passive"))
      (node (ref "JP7") (pin "13") (pinfunction "13_13") (pintype "passive"))
      (node (ref "U1") (pin "81") (pinfunction "PD12_81") (pintype "bidirectional"))
    )
    (net (code "95") (name "/PD13") (class "Default")
      (node (ref "JP3") (pin "14") (pinfunction "14_14") (pintype "passive"))
      (node (ref "JP7") (pin "14") (pinfunction "14_14") (pintype "passive"))
      (node (ref "U1") (pin "82") (pinfunction "PD13_82") (pintype "bidirectional"))
    )
    (net (code "96") (name "/PD14") (class "Default")
      (node (ref "JP3") (pin "17") (pinfunction "17_17") (pintype "passive"))
      (node (ref "JP7") (pin "17") (pinfunction "17_17") (pintype "passive"))
      (node (ref "U1") (pin "85") (pinfunction "PD14_85") (pintype "bidirectional"))
    )
    (net (code "97") (name "/PD15") (class "Default")
      (node (ref "JP3") (pin "18") (pinfunction "18_18") (pintype "passive"))
      (node (ref "JP7") (pin "18") (pinfunction "18_18") (pintype "passive"))
      (node (ref "U1") (pin "86") (pinfunction "PD15_86") (pintype "bidirectional"))
    )
    (net (code "98") (name "/PE0") (class "Default")
      (node (ref "JP4") (pin "33") (pinfunction "33_33") (pintype "passive"))
      (node (ref "JP8") (pin "33") (pinfunction "33_33") (pintype "passive"))
      (node (ref "U1") (pin "141") (pinfunction "PE0_141") (pintype "bidirectional"))
    )
    (net (code "99") (name "/PE1") (class "Default")
      (node (ref "JP4") (pin "34") (pinfunction "34_34") (pintype "passive"))
      (node (ref "JP8") (pin "34") (pinfunction "34_34") (pintype "passive"))
      (node (ref "U1") (pin "142") (pinfunction "PE1_142") (pintype "bidirectional"))
    )
    (net (code "100") (name "/PE2") (class "Default")
      (node (ref "JP1") (pin "5") (pinfunction "5_5") (pintype "passive"))
      (node (ref "JP5") (pin "5") (pinfunction "5_5") (pintype "passive"))
      (node (ref "U1") (pin "1") (pinfunction "PE2_1") (pintype "bidirectional"))
    )
    (net (code "101") (name "/PE3") (class "Default")
      (node (ref "JP1") (pin "6") (pinfunction "6_6") (pintype "passive"))
      (node (ref "JP5") (pin "6") (pinfunction "6_6") (pintype "passive"))
      (node (ref "U1") (pin "2") (pinfunction "PE3_2") (pintype "bidirectional"))
    )
    (net (code "102") (name "/PE4") (class "Default")
      (node (ref "JP1") (pin "7") (pinfunction "7_7") (pintype "passive"))
      (node (ref "JP5") (pin "7") (pinfunction "7_7") (pintype "passive"))
      (node (ref "U1") (pin "3") (pinfunction "PE4_3") (pintype "bidirectional"))
    )
    (net (code "103") (name "/PE5") (class "Default")
      (node (ref "JP1") (pin "8") (pinfunction "8_8") (pintype "passive"))
      (node (ref "JP5") (pin "8") (pinfunction "8_8") (pintype "passive"))
      (node (ref "U1") (pin "4") (pinfunction "PE5_4") (pintype "bidirectional"))
    )
    (net (code "104") (name "/PE6") (class "Default")
      (node (ref "JP1") (pin "9") (pinfunction "9_9") (pintype "passive"))
      (node (ref "JP5") (pin "9") (pinfunction "9_9") (pintype "passive"))
      (node (ref "U1") (pin "5") (pinfunction "PE6_5") (pintype "bidirectional"))
    )
    (net (code "105") (name "/PE7") (class "Default")
      (node (ref "JP2") (pin "22") (pinfunction "22_22") (pintype "passive"))
      (node (ref "JP6") (pin "22") (pinfunction "22_22") (pintype "passive"))
      (node (ref "U1") (pin "58") (pinfunction "PE7_58") (pintype "bidirectional"))
    )
    (net (code "106") (name "/PE8") (class "Default")
      (node (ref "JP2") (pin "23") (pinfunction "23_23") (pintype "passive"))
      (node (ref "JP6") (pin "23") (pinfunction "23_23") (pintype "passive"))
      (node (ref "U1") (pin "59") (pinfunction "PE8_59") (pintype "bidirectional"))
    )
    (net (code "107") (name "/PE9") (class "Default")
      (node (ref "JP2") (pin "24") (pinfunction "24_24") (pintype "passive"))
      (node (ref "JP6") (pin "24") (pinfunction "24_24") (pintype "passive"))
      (node (ref "U1") (pin "60") (pinfunction "PE9_60") (pintype "bidirectional"))
    )
    (net (code "108") (name "/PE10") (class "Default")
      (node (ref "JP2") (pin "27") (pinfunction "27_27") (pintype "passive"))
      (node (ref "JP6") (pin "27") (pinfunction "27_27") (pintype "passive"))
      (node (ref "U1") (pin "63") (pinfunction "PE10_63") (pintype "bidirectional"))
    )
    (net (code "109") (name "/PE11") (class "Default")
      (node (ref "JP2") (pin "28") (pinfunction "28_28") (pintype "passive"))
      (node (ref "JP6") (pin "28") (pinfunction "28_28") (pintype "passive"))
      (node (ref "U1") (pin "64") (pinfunction "PE11_64") (pintype "bidirectional"))
    )
    (net (code "110") (name "/PE12") (class "Default")
      (node (ref "JP2") (pin "29") (pinfunction "29_29") (pintype "passive"))
      (node (ref "JP6") (pin "29") (pinfunction "29_29") (pintype "passive"))
      (node (ref "U1") (pin "65") (pinfunction "PE12_65") (pintype "bidirectional"))
    )
    (net (code "111") (name "/PE13") (class "Default")
      (node (ref "JP2") (pin "30") (pinfunction "30_30") (pintype "passive"))
      (node (ref "JP6") (pin "30") (pinfunction "30_30") (pintype "passive"))
      (node (ref "U1") (pin "66") (pinfunction "PE13_66") (pintype "bidirectional"))
    )
    (net (code "112") (name "/PE14") (class "Default")
      (node (ref "JP2") (pin "31") (pinfunction "31_31") (pintype "passive"))
      (node (ref "JP6") (pin "31") (pinfunction "31_31") (pintype "passive"))
      (node (ref "U1") (pin "67") (pinfunction "PE14_67") (pintype "bidirectional"))
    )
    (net (code "113") (name "/PE15") (class "Default")
      (node (ref "JP2") (pin "32") (pinfunction "32_32") (pintype "passive"))
      (node (ref "JP6") (pin "32") (pinfunction "32_32") (pintype "passive"))
      (node (ref "U1") (pin "68") (pinfunction "PE15_68") (pintype "bidirectional"))
    )
    (net (code "114") (name "/PF0") (class "Default")
      (node (ref "JP1") (pin "14") (pinfunction "14_14") (pintype "passive"))
      (node (ref "JP5") (pin "14") (pinfunction "14_14") (pintype "passive"))
      (node (ref "U1") (pin "10") (pinfunction "PF0_10") (pintype "bidirectional"))
    )
    (net (code "115") (name "/PF1") (class "Default")
      (node (ref "JP1") (pin "15") (pinfunction "15_15") (pintype "passive"))
      (node (ref "JP5") (pin "15") (pinfunction "15_15") (pintype "passive"))
      (node (ref "U1") (pin "11") (pinfunction "PF1_11") (pintype "bidirectional"))
    )
    (net (code "116") (name "/PF2") (class "Default")
      (node (ref "JP1") (pin "16") (pinfunction "16_16") (pintype "passive"))
      (node (ref "JP5") (pin "16") (pinfunction "16_16") (pintype "passive"))
      (node (ref "U1") (pin "12") (pinfunction "PF2_12") (pintype "bidirectional"))
    )
    (net (code "117") (name "/PF3") (class "Default")
      (node (ref "JP1") (pin "17") (pinfunction "17_17") (pintype "passive"))
      (node (ref "JP5") (pin "17") (pinfunction "17_17") (pintype "passive"))
      (node (ref "U1") (pin "13") (pinfunction "PF3_13") (pintype "bidirectional"))
    )
    (net (code "118") (name "/PF4") (class "Default")
      (node (ref "JP1") (pin "18") (pinfunction "18_18") (pintype "passive"))
      (node (ref "JP5") (pin "18") (pinfunction "18_18") (pintype "passive"))
      (node (ref "U1") (pin "14") (pinfunction "PF4_14") (pintype "bidirectional"))
    )
    (net (code "119") (name "/PF5") (class "Default")
      (node (ref "JP1") (pin "19") (pinfunction "19_19") (pintype "passive"))
      (node (ref "JP5") (pin "19") (pinfunction "19_19") (pintype "passive"))
      (node (ref "U1") (pin "15") (pinfunction "PF5_15") (pintype "bidirectional"))
    )
    (net (code "120") (name "/PF6") (class "Default")
      (node (ref "JP1") (pin "22") (pinfunction "22_22") (pintype "passive"))
      (node (ref "JP5") (pin "22") (pinfunction "22_22") (pintype "passive"))
      (node (ref "U1") (pin "18") (pinfunction "PF6_18") (pintype "bidirectional"))
    )
    (net (code "121") (name "/PF7") (class "Default")
      (node (ref "JP1") (pin "23") (pinfunction "23_23") (pintype "passive"))
      (node (ref "JP5") (pin "23") (pinfunction "23_23") (pintype "passive"))
      (node (ref "U1") (pin "19") (pinfunction "PF7_19") (pintype "bidirectional"))
    )
    (net (code "122") (name "/PF8") (class "Default")
      (node (ref "JP1") (pin "24") (pinfunction "24_24") (pintype "passive"))
      (node (ref "JP5") (pin "24") (pinfunction "24_24") (pintype "passive"))
      (node (ref "U1") (pin "20") (pinfunction "PF8_20") (pintype "bidirectional"))
    )
    (net (code "123") (name "/PF9") (class "Default")
      (node (ref "JP1") (pin "25") (pinfunction "25_25") (pintype "passive"))
      (node (ref "JP5") (pin "25") (pinfunction "25_25") (pintype "passive"))
      (node (ref "U1") (pin "21") (pinfunction "PF9_21") (pintype "bidirectional"))
    )
    (net (code "124") (name "/PF10") (class "Default")
      (node (ref "JP1") (pin "26") (pinfunction "26_26") (pintype "passive"))
      (node (ref "JP5") (pin "26") (pinfunction "26_26") (pintype "passive"))
      (node (ref "U1") (pin "22") (pinfunction "PF10_22") (pintype "bidirectional"))
    )
    (net (code "125") (name "/PF11") (class "Default")
      (node (ref "JP2") (pin "13") (pinfunction "13_13") (pintype "passive"))
      (node (ref "JP6") (pin "13") (pinfunction "13_13") (pintype "passive"))
      (node (ref "U1") (pin "49") (pinfunction "PF11_49") (pintype "bidirectional"))
    )
    (net (code "126") (name "/PF12") (class "Default")
      (node (ref "JP2") (pin "14") (pinfunction "14_14") (pintype "passive"))
      (node (ref "JP6") (pin "14") (pinfunction "14_14") (pintype "passive"))
      (node (ref "U1") (pin "50") (pinfunction "PF12_50") (pintype "bidirectional"))
    )
    (net (code "127") (name "/PF13") (class "Default")
      (node (ref "JP2") (pin "17") (pinfunction "17_17") (pintype "passive"))
      (node (ref "JP6") (pin "17") (pinfunction "17_17") (pintype "passive"))
      (node (ref "U1") (pin "53") (pinfunction "PF13_53") (pintype "bidirectional"))
    )
    (net (code "128") (name "/PF14") (class "Default")
      (node (ref "JP2") (pin "18") (pinfunction "18_18") (pintype "passive"))
      (node (ref "JP6") (pin "18") (pinfunction "18_18") (pintype "passive"))
      (node (ref "U1") (pin "54") (pinfunction "PF14_54") (pintype "bidirectional"))
    )
    (net (code "129") (name "/PF15") (class "Default")
      (node (ref "JP2") (pin "19") (pinfunction "19_19") (pintype "passive"))
      (node (ref "JP6") (pin "19") (pinfunction "19_19") (pintype "passive"))
      (node (ref "U1") (pin "55") (pinfunction "PF15_55") (pintype "bidirectional"))
    )
    (net (code "130") (name "/PG0") (class "Default")
      (node (ref "JP2") (pin "20") (pinfunction "20_20") (pintype "passive"))
      (node (ref "JP6") (pin "20") (pinfunction "20_20") (pintype "passive"))
      (node (ref "U1") (pin "56") (pinfunction "PG0_56") (pintype "bidirectional"))
    )
    (net (code "131") (name "/PG1") (class "Default")
      (node (ref "JP2") (pin "21") (pinfunction "21_21") (pintype "passive"))
      (node (ref "JP6") (pin "21") (pinfunction "21_21") (pintype "passive"))
      (node (ref "U1") (pin "57") (pinfunction "PG1_57") (pintype "bidirectional"))
    )
    (net (code "132") (name "/PG2") (class "Default")
      (node (ref "JP3") (pin "19") (pinfunction "19_19") (pintype "passive"))
      (node (ref "JP7") (pin "19") (pinfunction "19_19") (pintype "passive"))
      (node (ref "U1") (pin "87") (pinfunction "PG2_87") (pintype "bidirectional"))
    )
    (net (code "133") (name "/PG3") (class "Default")
      (node (ref "JP3") (pin "20") (pinfunction "20_20") (pintype "passive"))
      (node (ref "JP7") (pin "20") (pinfunction "20_20") (pintype "passive"))
      (node (ref "U1") (pin "88") (pinfunction "PG3_88") (pintype "bidirectional"))
    )
    (net (code "134") (name "/PG4") (class "Default")
      (node (ref "JP3") (pin "21") (pinfunction "21_21") (pintype "passive"))
      (node (ref "JP7") (pin "21") (pinfunction "21_21") (pintype "passive"))
      (node (ref "U1") (pin "89") (pinfunction "PG4_89") (pintype "bidirectional"))
    )
    (net (code "135") (name "/PG5") (class "Default")
      (node (ref "JP3") (pin "22") (pinfunction "22_22") (pintype "passive"))
      (node (ref "JP7") (pin "22") (pinfunction "22_22") (pintype "passive"))
      (node (ref "U1") (pin "90") (pinfunction "PG5_90") (pintype "bidirectional"))
    )
    (net (code "136") (name "/PG6") (class "Default")
      (node (ref "JP3") (pin "23") (pinfunction "23_23") (pintype "passive"))
      (node (ref "JP7") (pin "23") (pinfunction "23_23") (pintype "passive"))
      (node (ref "U1") (pin "91") (pinfunction "PG6_91") (pintype "bidirectional"))
    )
    (net (code "137") (name "/PG7") (class "Default")
      (node (ref "JP3") (pin "24") (pinfunction "24_24") (pintype "passive"))
      (node (ref "JP7") (pin "24") (pinfunction "24_24") (pintype "passive"))
      (node (ref "U1") (pin "92") (pinfunction "PG7_92") (pintype "bidirectional"))
    )
    (net (code "138") (name "/PG8") (class "Default")
      (node (ref "JP3") (pin "25") (pinfunction "25_25") (pintype "passive"))
      (node (ref "JP7") (pin "25") (pinfunction "25_25") (pintype "passive"))
      (node (ref "U1") (pin "93") (pinfunction "PG8_93") (pintype "bidirectional"))
    )
    (net (code "139") (name "/PG9") (class "Default")
      (node (ref "JP4") (pin "16") (pinfunction "16_16") (pintype "passive"))
      (node (ref "JP8") (pin "16") (pinfunction "16_16") (pintype "passive"))
      (node (ref "U1") (pin "124") (pinfunction "PG9_124") (pintype "bidirectional"))
    )
    (net (code "140") (name "/PG10") (class "Default")
      (node (ref "JP4") (pin "17") (pinfunction "17_17") (pintype "passive"))
      (node (ref "JP8") (pin "17") (pinfunction "17_17") (pintype "passive"))
      (node (ref "U1") (pin "125") (pinfunction "PG10_125") (pintype "bidirectional"))
    )
    (net (code "141") (name "/PG11") (class "Default")
      (node (ref "JP4") (pin "18") (pinfunction "18_18") (pintype "passive"))
      (node (ref "JP8") (pin "18") (pinfunction "18_18") (pintype "passive"))
      (node (ref "U1") (pin "126") (pinfunction "PG11_126") (pintype "bidirectional"))
    )
    (net (code "142") (name "/PG12") (class "Default")
      (node (ref "JP4") (pin "19") (pinfunction "19_19") (pintype "passive"))
      (node (ref "JP8") (pin "19") (pinfunction "19_19") (pintype "passive"))
      (node (ref "U1") (pin "127") (pinfunction "PG12_127") (pintype "bidirectional"))
    )
    (net (code "143") (name "/PG13") (class "Default")
      (node (ref "JP4") (pin "20") (pinfunction "20_20") (pintype "passive"))
      (node (ref "JP8") (pin "20") (pinfunction "20_20") (pintype "passive"))
      (node (ref "U1") (pin "128") (pinfunction "PG13_128") (pintype "bidirectional"))
    )
    (net (code "144") (name "/PG14") (class "Default")
      (node (ref "JP4") (pin "21") (pinfunction "21_21") (pintype "passive"))
      (node (ref "JP8") (pin "21") (pinfunction "21_21") (pintype "passive"))
      (node (ref "U1") (pin "129") (pinfunction "PG14_129") (pintype "bidirectional"))
    )
    (net (code "145") (name "/PG15") (class "Default")
      (node (ref "JP4") (pin "24") (pinfunction "24_24") (pintype "passive"))
      (node (ref "JP8") (pin "24") (pinfunction "24_24") (pintype "passive"))
      (node (ref "U1") (pin "132") (pinfunction "PG15_132") (pintype "bidirectional"))
    )
    (net (code "146") (name "/PH0") (class "Default")
      (node (ref "C2") (pin "2") (pinfunction "2_2") (pintype "passive"))
      (node (ref "JP1") (pin "27") (pinfunction "27_27") (pintype "passive"))
      (node (ref "JP5") (pin "27") (pinfunction "27_27") (pintype "passive"))
      (node (ref "U1") (pin "23") (pinfunction "PH0-OSC_IN_23") (pintype "bidirectional"))
      (node (ref "Y1") (pin "2") (pinfunction "OSC2_2") (pintype "passive"))
    )
    (net (code "147") (name "/PH1") (class "Default")
      (node (ref "C1") (pin "2") (pinfunction "2_2") (pintype "passive"))
      (node (ref "JP1") (pin "28") (pinfunction "28_28") (pintype "passive"))
      (node (ref "JP5") (pin "28") (pinfunction "28_28") (pintype "passive"))
      (node (ref "U1") (pin "24") (pinfunction "PH1-OSC_OUT_24") (pintype "bidirectional"))
      (node (ref "Y1") (pin "1") (pinfunction "OSC1_1") (pintype "passive"))
    )
    (net (code "148") (name "/RFU") (class "Default")
      (node (ref "JP4") (pin "35") (pinfunction "35_35") (pintype "passive"))
      (node (ref "JP8") (pin "35") (pinfunction "35_35") (pintype "passive"))
      (node (ref "U1") (pin "143") (pinfunction "RFU_143") (pintype "passive"))
    )
    (net (code "149") (name "/VBAT") (class "Default")
      (node (ref "JP1") (pin "10") (pinfunction "10_10") (pintype "passive"))
      (node (ref "JP5") (pin "10") (pinfunction "10_10") (pintype "passive"))
      (node (ref "U1") (pin "6") (pinfunction "VBAT_6") (pintype "power_in"))
    )
    (net (code "150") (name "/VCAP_1") (class "Default")
      (node (ref "C11") (pin "1") (pinfunction "1_1") (pintype "passive"))
      (node (ref "JP2") (pin "35") (pinfunction "35_35") (pintype "passive"))
      (node (ref "JP6") (pin "35") (pinfunction "35_35") (pintype "passive"))
      (node (ref "U1") (pin "71") (pinfunction "VCAP_1_71") (pintype "passive"))
    )
    (net (code "151") (name "/VCAP_2") (class "Default")
      (node (ref "C12") (pin "1") (pinfunction "1_1") (pintype "passive"))
      (node (ref "JP3") (pin "38") (pinfunction "38_38") (pintype "passive"))
      (node (ref "JP7") (pin "38") (pinfunction "38_38") (pintype "passive"))
      (node (ref "U1") (pin "106") (pinfunction "VCAP_2_106") (pintype "passive"))
    )
    (net (code "152") (name "/VREF+") (class "Default")
      (node (ref "JP1") (pin "36") (pinfunction "36_36") (pintype "passive"))
      (node (ref "JP5") (pin "36") (pinfunction "36_36") (pintype "passive"))
      (node (ref "U1") (pin "32") (pinfunction "VREF+_32") (pintype "power_in"))
    )
    (net (code "153") (name "/Vcc_sram") (class "Default")
      (node (ref "C5") (pin "2") (pinfunction "2_2") (pintype "passive"))
      (node (ref "C6") (pin "2") (pinfunction "2_2") (pintype "passive"))
      (node (ref "JP12") (pin "9") (pinfunction "9_9") (pintype "passive"))
      (node (ref "JP13") (pin "8") (pinfunction "8_8") (pintype "passive"))
      (node (ref "JP14") (pin "9") (pinfunction "9_9") (pintype "passive"))
      (node (ref "JP15") (pin "8") (pinfunction "8_8") (pintype "passive"))
      (node (ref "U3") (pin "11") (pinfunction "VCC1_11") (pintype "passive"))
      (node (ref "U3") (pin "33") (pinfunction "VCC2_33") (pintype "passive"))
    )
    (net (code "154") (name "/WE") (class "Default")
      (node (ref "U3") (pin "15") (pinfunction "~{WE}_15") (pintype "passive"))
    )
    (net (code "155") (name "GND") (class "Default")
      (node (ref "C1") (pin "1") (pinfunction "1_1") (pintype "passive"))
      (node (ref "C10") (pin "2") (pinfunction "2_2") (pintype "passive"))
      (node (ref "C11") (pin "2") (pinfunction "2_2") (pintype "passive"))
      (node (ref "C12") (pin "2") (pinfunction "2_2") (pintype "passive"))
      (node (ref "C13") (pin "1") (pinfunction "1_1") (pintype "passive"))
      (node (ref "C14") (pin "1") (pinfunction "1_1") (pintype "passive"))
      (node (ref "C15") (pin "1") (pinfunction "1_1") (pintype "passive"))
      (node (ref "C16") (pin "1") (pinfunction "1_1") (pintype "passive"))
      (node (ref "C17") (pin "1") (pinfunction "1_1") (pintype "passive"))
      (node (ref "C18") (pin "1") (pinfunction "1_1") (pintype "passive"))
      (node (ref "C2") (pin "1") (pinfunction "1_1") (pintype "passive"))
      (node (ref "C3") (pin "1") (pinfunction "1_1") (pintype "passive"))
      (node (ref "C33") (pin "2") (pinfunction "2_2") (pintype "passive"))
      (node (ref "C4") (pin "1") (pinfunction "1_1") (pintype "passive"))
      (node (ref "C7") (pin "2") (pinfunction "2_2") (pintype "passive"))
      (node (ref "C8") (pin "2") (pinfunction "2_2") (pintype "passive"))
      (node (ref "C9") (pin "2") (pinfunction "2_2") (pintype "passive"))
      (node (ref "JP1") (pin "20") (pinfunction "20_20") (pintype "passive"))
      (node (ref "JP1") (pin "35") (pinfunction "35_35") (pintype "passive"))
      (node (ref "JP11") (pin "10") (pinfunction "10_10") (pintype "passive"))
      (node (ref "JP11") (pin "12") (pinfunction "12_12") (pintype "passive"))
      (node (ref "JP11") (pin "14") (pinfunction "14_14") (pintype "passive"))
      (node (ref "JP11") (pin "16") (pinfunction "16_16") (pintype "passive"))
      (node (ref "JP11") (pin "18") (pinfunction "18_18") (pintype "passive"))
      (node (ref "JP11") (pin "20") (pinfunction "20_20") (pintype "passive"))
      (node (ref "JP11") (pin "4") (pinfunction "4_4") (pintype "passive"))
      (node (ref "JP11") (pin "6") (pinfunction "6_6") (pintype "passive"))
      (node (ref "JP11") (pin "8") (pinfunction "8_8") (pintype "passive"))
      (node (ref "JP2") (pin "15") (pinfunction "15_15") (pintype "passive"))
      (node (ref "JP2") (pin "2") (pinfunction "2_2") (pintype "passive"))
      (node (ref "JP2") (pin "25") (pinfunction "25_25") (pintype "passive"))
      (node (ref "JP3") (pin "15") (pinfunction "15_15") (pintype "passive"))
      (node (ref "JP3") (pin "26") (pinfunction "26_26") (pintype "passive"))
      (node (ref "JP3") (pin "39") (pinfunction "39_39") (pintype "passive"))
      (node (ref "JP4") (pin "12") (pinfunction "12_12") (pintype "passive"))
      (node (ref "JP4") (pin "22") (pinfunction "22_22") (pintype "passive"))
      (node (ref "JP5") (pin "20") (pinfunction "20_20") (pintype "passive"))
      (node (ref "JP5") (pin "35") (pinfunction "35_35") (pintype "passive"))
      (node (ref "JP6") (pin "15") (pinfunction "15_15") (pintype "passive"))
      (node (ref "JP6") (pin "2") (pinfunction "2_2") (pintype "passive"))
      (node (ref "JP6") (pin "25") (pinfunction "25_25") (pintype "passive"))
      (node (ref "JP7") (pin "15") (pinfunction "15_15") (pintype "passive"))
      (node (ref "JP7") (pin "26") (pinfunction "26_26") (pintype "passive"))
      (node (ref "JP7") (pin "39") (pinfunction "39_39") (pintype "passive"))
      (node (ref "JP8") (pin "12") (pinfunction "12_12") (pintype "passive"))
      (node (ref "JP8") (pin "22") (pinfunction "22_22") (pintype "passive"))
      (node (ref "R1") (pin "2") (pinfunction "2_2") (pintype "passive"))
      (node (ref "R2") (pin "2") (pinfunction "2_2") (pintype "passive"))
      (node (ref "R3") (pin "2") (pinfunction "2_2") (pintype "passive"))
      (node (ref "R4") (pin "2") (pinfunction "2_2") (pintype "passive"))
      (node (ref "U1") (pin "107") (pinfunction "VSS_2_107") (pintype "power_in"))
      (node (ref "U1") (pin "120") (pinfunction "VSS_10_120") (pintype "power_in"))
      (node (ref "U1") (pin "130") (pinfunction "VSS_11_130") (pintype "power_in"))
      (node (ref "U1") (pin "16") (pinfunction "VSS_5_16") (pintype "power_in"))
      (node (ref "U1") (pin "31") (pinfunction "VSSA_31") (pintype "power_in"))
      (node (ref "U1") (pin "38") (pinfunction "VSS_4_38") (pintype "power_in"))
      (node (ref "U1") (pin "51") (pinfunction "VSS_6_51") (pintype "power_in"))
      (node (ref "U1") (pin "61") (pinfunction "VSS_7_61") (pintype "power_in"))
      (node (ref "U1") (pin "83") (pinfunction "VSS_8_83") (pintype "power_in"))
      (node (ref "U1") (pin "94") (pinfunction "VSS_9_94") (pintype "power_in"))
      (node (ref "U12") (pin "2") (pinfunction "Vdd_2") (pintype "passive"))
    )
    (net (code "156") (name "Net-(JP1-Pad1)") (class "Default")
      (node (ref "JP1") (pin "1") (pinfunction "1_1") (pintype "passive"))
      (node (ref "JP5") (pin "1") (pinfunction "1_1") (pintype "passive"))
    )
    (net (code "157") (name "Net-(JP1-Pad2)") (class "Default")
      (node (ref "JP1") (pin "2") (pinfunction "2_2") (pintype "passive"))
      (node (ref "JP5") (pin "2") (pinfunction "2_2") (pintype "passive"))
    )
    (net (code "158") (name "Net-(JP1-Pad3)") (class "Default")
      (node (ref "JP1") (pin "3") (pinfunction "3_3") (pintype "passive"))
      (node (ref "JP5") (pin "3") (pinfunction "3_3") (pintype "passive"))
    )
    (net (code "159") (name "Net-(JP1-Pad4)") (class "Default")
      (node (ref "JP1") (pin "4") (pinfunction "4_4") (pintype "passive"))
      (node (ref "JP5") (pin "4") (pinfunction "4_4") (pintype "passive"))
    )
    (net (code "160") (name "Net-(JP2-Pad37)") (class "Default")
      (node (ref "JP2") (pin "37") (pinfunction "37_37") (pintype "passive"))
      (node (ref "JP6") (pin "37") (pinfunction "37_37") (pintype "passive"))
    )
    (net (code "161") (name "Net-(JP2-Pad38)") (class "Default")
      (node (ref "JP2") (pin "38") (pinfunction "38_38") (pintype "passive"))
      (node (ref "JP6") (pin "38") (pinfunction "38_38") (pintype "passive"))
    )
    (net (code "162") (name "Net-(JP2-Pad39)") (class "Default")
      (node (ref "JP2") (pin "39") (pinfunction "39_39") (pintype "passive"))
      (node (ref "JP6") (pin "39") (pinfunction "39_39") (pintype "passive"))
    )
    (net (code "163") (name "Net-(JP2-Pad40)") (class "Default")
      (node (ref "JP2") (pin "40") (pinfunction "40_40") (pintype "passive"))
      (node (ref "JP6") (pin "40") (pinfunction "40_40") (pintype "passive"))
    )
    (net (code "164") (name "Net-(JP3-Pad1)") (class "Default")
      (node (ref "JP3") (pin "1") (pinfunction "1_1") (pintype "passive"))
      (node (ref "JP7") (pin "1") (pinfunction "1_1") (pintype "passive"))
    )
    (net (code "165") (name "Net-(JP3-Pad2)") (class "Default")
      (node (ref "JP3") (pin "2") (pinfunction "2_2") (pintype "passive"))
      (node (ref "JP7") (pin "2") (pinfunction "2_2") (pintype "passive"))
    )
    (net (code "166") (name "Net-(JP3-Pad3)") (class "Default")
      (node (ref "JP3") (pin "3") (pinfunction "3_3") (pintype "passive"))
      (node (ref "JP7") (pin "3") (pinfunction "3_3") (pintype "passive"))
    )
    (net (code "167") (name "Net-(JP3-Pad4)") (class "Default")
      (node (ref "JP3") (pin "4") (pinfunction "4_4") (pintype "passive"))
      (node (ref "JP7") (pin "4") (pinfunction "4_4") (pintype "passive"))
    )
    (net (code "168") (name "Net-(JP4-Pad37)") (class "Default")
      (node (ref "JP4") (pin "37") (pinfunction "37_37") (pintype "passive"))
      (node (ref "JP8") (pin "37") (pinfunction "37_37") (pintype "passive"))
    )
    (net (code "169") (name "Net-(JP4-Pad38)") (class "Default")
      (node (ref "JP4") (pin "38") (pinfunction "38_38") (pintype "passive"))
      (node (ref "JP8") (pin "38") (pinfunction "38_38") (pintype "passive"))
    )
    (net (code "170") (name "Net-(JP4-Pad39)") (class "Default")
      (node (ref "JP4") (pin "39") (pinfunction "39_39") (pintype "passive"))
      (node (ref "JP8") (pin "39") (pinfunction "39_39") (pintype "passive"))
    )
    (net (code "171") (name "Net-(JP4-Pad40)") (class "Default")
      (node (ref "JP4") (pin "40") (pinfunction "40_40") (pintype "passive"))
      (node (ref "JP8") (pin "40") (pinfunction "40_40") (pintype "passive"))
    )
    (net (code "172") (name "Net-(JP10-Pad1)") (class "Default")
      (node (ref "JP10") (pin "1") (pinfunction "1_1") (pintype "passive"))
      (node (ref "JP9") (pin "1") (pinfunction "1_1") (pintype "passive"))
    )
    (net (code "173") (name "Net-(JP10-Pad2)") (class "Default")
      (node (ref "JP10") (pin "2") (pinfunction "2_2") (pintype "passive"))
      (node (ref "JP9") (pin "2") (pinfunction "2_2") (pintype "passive"))
    )
    (net (code "174") (name "Net-(JP10-Pad3)") (class "Default")
      (node (ref "JP10") (pin "3") (pinfunction "3_3") (pintype "passive"))
      (node (ref "JP9") (pin "3") (pinfunction "3_3") (pintype "passive"))
    )
    (net (code "175") (name "Net-(JP10-Pad4)") (class "Default")
      (node (ref "JP10") (pin "4") (pinfunction "4_4") (pintype "passive"))
      (node (ref "JP9") (pin "4") (pinfunction "4_4") (pintype "passive"))
    )
    (net (code "176") (name "Net-(JP10-Pad5)") (class "Default")
      (node (ref "JP10") (pin "5") (pinfunction "5_5") (pintype "passive"))
      (node (ref "JP9") (pin "5") (pinfunction "5_5") (pintype "passive"))
    )
    (net (code "177") (name "Net-(JP10-Pad6)") (class "Default")
      (node (ref "JP10") (pin "6") (pinfunction "6_6") (pintype "passive"))
      (node (ref "JP9") (pin "6") (pinfunction "6_6") (pintype "passive"))
    )
    (net (code "178") (name "Net-(JP10-Pad7)") (class "Default")
      (node (ref "JP10") (pin "7") (pinfunction "7_7") (pintype "passive"))
      (node (ref "JP9") (pin "7") (pinfunction "7_7") (pintype "passive"))
    )
    (net (code "179") (name "Net-(JP10-Pad8)") (class "Default")
      (node (ref "JP10") (pin "8") (pinfunction "8_8") (pintype "passive"))
      (node (ref "JP9") (pin "8") (pinfunction "8_8") (pintype "passive"))
    )
    (net (code "180") (name "Net-(JP10-Pad9)") (class "Default")
      (node (ref "JP10") (pin "9") (pinfunction "9_9") (pintype "passive"))
      (node (ref "JP9") (pin "9") (pinfunction "9_9") (pintype "passive"))
    )
    (net (code "181") (name "Net-(JP10-Pad10)") (class "Default")
      (node (ref "JP10") (pin "10") (pinfunction "10_10") (pintype "passive"))
      (node (ref "JP9") (pin "10") (pinfunction "10_10") (pintype "passive"))
    )
    (net (code "182") (name "Net-(JP10-Pad11)") (class "Default")
      (node (ref "JP10") (pin "11") (pinfunction "11_11") (pintype "passive"))
      (node (ref "JP9") (pin "11") (pinfunction "11_11") (pintype "passive"))
    )
    (net (code "183") (name "Net-(JP10-Pad12)") (class "Default")
      (node (ref "JP10") (pin "12") (pinfunction "12_12") (pintype "passive"))
      (node (ref "JP9") (pin "12") (pinfunction "12_12") (pintype "passive"))
    )
    (net (code "184") (name "Net-(JP10-Pad13)") (class "Default")
      (node (ref "JP10") (pin "13") (pinfunction "13_13") (pintype "passive"))
      (node (ref "JP9") (pin "13") (pinfunction "13_13") (pintype "passive"))
    )
    (net (code "185") (name "Net-(JP10-Pad14)") (class "Default")
      (node (ref "JP10") (pin "14") (pinfunction "14_14") (pintype "passive"))
      (node (ref "JP9") (pin "14") (pinfunction "14_14") (pintype "passive"))
    )
    (net (code "186") (name "Net-(JP10-Pad15)") (class "Default")
      (node (ref "JP10") (pin "15") (pinfunction "15_15") (pintype "passive"))
      (node (ref "JP9") (pin "15") (pinfunction "15_15") (pintype "passive"))
    )
    (net (code "187") (name "Net-(JP10-Pad16)") (class "Default")
      (node (ref "JP10") (pin "16") (pinfunction "16_16") (pintype "passive"))
      (node (ref "JP9") (pin "16") (pinfunction "16_16") (pintype "passive"))
    )
    (net (code "188") (name "Net-(JP10-Pad17)") (class "Default")
      (node (ref "JP10") (pin "17") (pinfunction "17_17") (pintype "passive"))
      (node (ref "JP9") (pin "17") (pinfunction "17_17") (pintype "passive"))
    )
    (net (code "189") (name "Net-(JP10-Pad18)") (class "Default")
      (node (ref "JP10") (pin "18") (pinfunction "18_18") (pintype "passive"))
      (node (ref "JP9") (pin "18") (pinfunction "18_18") (pintype "passive"))
    )
    (net (code "190") (name "Net-(JP10-Pad19)") (class "Default")
      (node (ref "JP10") (pin "19") (pinfunction "19_19") (pintype "passive"))
      (node (ref "JP9") (pin "19") (pinfunction "19_19") (pintype "passive"))
    )
    (net (code "191") (name "Net-(JP10-Pad20)") (class "Default")
      (node (ref "JP10") (pin "20") (pinfunction "20_20") (pintype "passive"))
      (node (ref "JP9") (pin "20") (pinfunction "20_20") (pintype "passive"))
    )
    (net (code "192") (name "Net-(JP10-Pad21)") (class "Default")
      (node (ref "JP10") (pin "21") (pinfunction "21_21") (pintype "passive"))
      (node (ref "JP9") (pin "21") (pinfunction "21_21") (pintype "passive"))
    )
    (net (code "193") (name "Net-(JP10-Pad22)") (class "Default")
      (node (ref "JP10") (pin "22") (pinfunction "22_22") (pintype "passive"))
      (node (ref "JP9") (pin "22") (pinfunction "22_22") (pintype "passive"))
    )
    (net (code "194") (name "Net-(JP10-Pad23)") (class "Default")
      (node (ref "JP10") (pin "23") (pinfunction "23_23") (pintype "passive"))
      (node (ref "JP9") (pin "23") (pinfunction "23_23") (pintype "passive"))
    )
    (net (code "195") (name "Net-(JP10-Pad24)") (class "Default")
      (node (ref "JP10") (pin "24") (pinfunction "24_24") (pintype "passive"))
      (node (ref "JP9") (pin "24") (pinfunction "24_24") (pintype "passive"))
    )
    (net (code "196") (name "Net-(JP10-Pad25)") (class "Default")
      (node (ref "JP10") (pin "25") (pinfunction "25_25") (pintype "passive"))
      (node (ref "JP9") (pin "25") (pinfunction "25_25") (pintype "passive"))
    )
    (net (code "197") (name "Net-(JP10-Pad26)") (class "Default")
      (node (ref "JP10") (pin "26") (pinfunction "26_26") (pintype "passive"))
      (node (ref "JP9") (pin "26") (pinfunction "26_26") (pintype "passive"))
    )
    (net (code "198") (name "Net-(JP10-Pad27)") (class "Default")
      (node (ref "JP10") (pin "27") (pinfunction "27_27") (pintype "passive"))
      (node (ref "JP9") (pin "27") (pinfunction "27_27") (pintype "passive"))
    )
    (net (code "199") (name "Net-(JP10-Pad28)") (class "Default")
      (node (ref "JP10") (pin "28") (pinfunction "28_28") (pintype "passive"))
      (node (ref "JP9") (pin "28") (pinfunction "28_28") (pintype "passive"))
    )
    (net (code "200") (name "Net-(JP10-Pad29)") (class "Default")
      (node (ref "JP10") (pin "29") (pinfunction "29_29") (pintype "passive"))
      (node (ref "JP9") (pin "29") (pinfunction "29_29") (pintype "passive"))
    )
    (net (code "201") (name "Net-(JP10-Pad30)") (class "Default")
      (node (ref "JP10") (pin "30") (pinfunction "30_30") (pintype "passive"))
      (node (ref "JP9") (pin "30") (pinfunction "30_30") (pintype "passive"))
    )
    (net (code "202") (name "Net-(JP10-Pad31)") (class "Default")
      (node (ref "JP10") (pin "31") (pinfunction "31_31") (pintype "passive"))
      (node (ref "JP9") (pin "31") (pinfunction "31_31") (pintype "passive"))
    )
    (net (code "203") (name "Net-(JP10-Pad32)") (class "Default")
      (node (ref "JP10") (pin "32") (pinfunction "32_32") (pintype "passive"))
      (node (ref "JP9") (pin "32") (pinfunction "32_32") (pintype "passive"))
    )
    (net (code "204") (name "Net-(JP10-Pad33)") (class "Default")
      (node (ref "JP10") (pin "33") (pinfunction "33_33") (pintype "passive"))
      (node (ref "JP9") (pin "33") (pinfunction "33_33") (pintype "passive"))
    )
    (net (code "205") (name "Net-(JP10-Pad34)") (class "Default")
      (node (ref "JP10") (pin "34") (pinfunction "34_34") (pintype "passive"))
      (node (ref "JP9") (pin "34") (pinfunction "34_34") (pintype "passive"))
    )
    (net (code "206") (name "Net-(JP10-Pad35)") (class "Default")
      (node (ref "JP10") (pin "35") (pinfunction "35_35") (pintype "passive"))
      (node (ref "JP9") (pin "35") (pinfunction "35_35") (pintype "passive"))
    )
    (net (code "207") (name "Net-(JP10-Pad36)") (class "Default")
      (node (ref "JP10") (pin "36") (pinfunction "36_36") (pintype "passive"))
      (node (ref "JP9") (pin "36") (pinfunction "36_36") (pintype "passive"))
    )
    (net (code "208") (name "Net-(JP11-Pad11)") (class "Default")
      (node (ref "JP11") (pin "11") (pinfunction "11_11") (pintype "passive"))
      (node (ref "R3") (pin "1") (pinfunction "1_1") (pintype "passive"))
    )
    (net (code "209") (name "Net-(JP11-Pad17)") (class "Default")
      (node (ref "JP11") (pin "17") (pinfunction "17_17") (pintype "passive"))
      (node (ref "R2") (pin "1") (pinfunction "1_1") (pintype "passive"))
    )
    (net (code "210") (name "Net-(JP11-Pad19)") (class "Default")
      (node (ref "JP11") (pin "19") (pinfunction "19_19") (pintype "passive"))
      (node (ref "R4") (pin "1") (pinfunction "1_1") (pintype "passive"))
    )
    (net (code "211") (name "Net-(JP18-Pad1)") (class "Default")
      (node (ref "JP18") (pin "1") (pinfunction "1_1") (pintype "passive"))
      (node (ref "JP19") (pin "1") (pinfunction "1_1") (pintype "passive"))
      (node (ref "U2") (pin "16") (pinfunction "DIN_16") (pintype "passive"))
    )
    (net (code "212") (name "Net-(JP18-Pad3)") (class "Default")
      (node (ref "JP18") (pin "3") (pinfunction "3_3") (pintype "passive"))
      (node (ref "JP19") (pin "3") (pinfunction "3_3") (pintype "passive"))
      (node (ref "U2") (pin "14") (pinfunction "DIN_14") (pintype "passive"))
    )
    (net (code "213") (name "Net-(JP20-Pad1)") (class "Default")
      (node (ref "JP20") (pin "1") (pinfunction "1_1") (pintype "passive"))
      (node (ref "JP21") (pin "1") (pinfunction "1_1") (pintype "passive"))
      (node (ref "JP22") (pin "1") (pinfunction "1_1") (pintype "passive"))
      (node (ref "JP23") (pin "1") (pinfunction "1_1") (pintype "passive"))
      (node (ref "JP24") (pin "1") (pinfunction "1_1") (pintype "passive"))
    )
    (net (code "214") (name "Net-(JP20-Pad2)") (class "Default")
      (node (ref "JP20") (pin "2") (pinfunction "2_2") (pintype "passive"))
      (node (ref "JP21") (pin "2") (pinfunction "2_2") (pintype "passive"))
      (node (ref "JP22") (pin "2") (pinfunction "2_2") (pintype "passive"))
      (node (ref "JP23") (pin "2") (pinfunction "2_2") (pintype "passive"))
      (node (ref "JP24") (pin "2") (pinfunction "2_2") (pintype "passive"))
    )
    (net (code "215") (name "Net-(JP20-Pad3)") (class "Default")
      (node (ref "JP20") (pin "3") (pinfunction "3_3") (pintype "passive"))
      (node (ref "JP21") (pin "3") (pinfunction "3_3") (pintype "passive"))
      (node (ref "JP22") (pin "3") (pinfunction "3_3") (pintype "passive"))
      (node (ref "JP23") (pin "3") (pinfunction "3_3") (pintype "passive"))
      (node (ref "JP24") (pin "3") (pinfunction "3_3") (pintype "passive"))
    )
    (net (code "216") (name "Net-(JP25-Pad1)") (class "Default")
      (node (ref "JP25") (pin "1") (pinfunction "1_1") (pintype "passive"))
      (node (ref "JP26") (pin "1") (pinfunction "1_1") (pintype "passive"))
      (node (ref "JP27") (pin "1") (pinfunction "1_1") (pintype "passive"))
      (node (ref "JP28") (pin "1") (pinfunction "1_1") (pintype "passive"))
      (node (ref "JP29") (pin "1") (pinfunction "1_1") (pintype "passive"))
    )
    (net (code "217") (name "Net-(JP25-Pad2)") (class "Default")
      (node (ref "JP25") (pin "2") (pinfunction "2_2") (pintype "passive"))
      (node (ref "JP26") (pin "2") (pinfunction "2_2") (pintype "passive"))
      (node (ref "JP27") (pin "2") (pinfunction "2_2") (pintype "passive"))
      (node (ref "JP28") (pin "2") (pinfunction "2_2") (pintype "passive"))
      (node (ref "JP29") (pin "2") (pinfunction "2_2") (pintype "passive"))
    )
    (net (code "218") (name "Net-(JP25-Pad3)") (class "Default")
      (node (ref "JP25") (pin "3") (pinfunction "3_3") (pintype "passive"))
      (node (ref "JP26") (pin "3") (pinfunction "3_3") (pintype "passive"))
      (node (ref "JP27") (pin "3") (pinfunction "3_3") (pintype "passive"))
      (node (ref "JP28") (pin "3") (pinfunction "3_3") (pintype "passive"))
      (node (ref "JP29") (pin "3") (pinfunction "3_3") (pintype "passive"))
    )
    (net (code "219") (name "Net-(JP30-Pad1)") (class "Default")
      (node (ref "JP30") (pin "1") (pinfunction "1_1") (pintype "passive"))
      (node (ref "JP31") (pin "1") (pinfunction "1_1") (pintype "passive"))
      (node (ref "JP32") (pin "1") (pinfunction "1_1") (pintype "passive"))
      (node (ref "JP33") (pin "1") (pinfunction "1_1") (pintype "passive"))
      (node (ref "JP34") (pin "1") (pinfunction "1_1") (pintype "passive"))
    )
    (net (code "220") (name "Net-(JP30-Pad2)") (class "Default")
      (node (ref "JP30") (pin "2") (pinfunction "2_2") (pintype "passive"))
      (node (ref "JP31") (pin "2") (pinfunction "2_2") (pintype "passive"))
      (node (ref "JP32") (pin "2") (pinfunction "2_2") (pintype "passive"))
      (node (ref "JP33") (pin "2") (pinfunction "2_2") (pintype "passive"))
      (node (ref "JP34") (pin "2") (pinfunction "2_2") (pintype "passive"))
    )
    (net (code "221") (name "Net-(JP35-Pad1)") (class "Default")
      (node (ref "JP35") (pin "1") (pinfunction "1_1") (pintype "passive"))
      (node (ref "JP36") (pin "1") (pinfunction "1_1") (pintype "passive"))
      (node (ref "JP37") (pin "1") (pinfunction "1_1") (pintype "passive"))
      (node (ref "JP38") (pin "1") (pinfunction "1_1") (pintype "passive"))
      (node (ref "JP39") (pin "1") (pinfunction "1_1") (pintype "passive"))
    )
    (net (code "222") (name "Net-(JP35-Pad2)") (class "Default")
      (node (ref "JP35") (pin "2") (pinfunction "2_2") (pintype "passive"))
      (node (ref "JP36") (pin "2") (pinfunction "2_2") (pintype "passive"))
      (node (ref "JP37") (pin "2") (pinfunction "2_2") (pintype "passive"))
      (node (ref "JP38") (pin "2") (pinfunction "2_2") (pintype "passive"))
      (node (ref "JP39") (pin "2") (pinfunction "2_2") (pintype "passive"))
    )
    (net (code "223") (name "Net-(U2-AUX)") (class "Default")
      (node (ref "JP16") (pin "8") (pinfunction "8_8") (pintype "passive"))
      (node (ref "JP17") (pin "8") (pinfunction "8_8") (pintype "passive"))
      (node (ref "U2") (pin "8") (pinfunction "AUX_8") (pintype "passive"))
    )
    (net (code "224") (name "Net-(U2-BUSY)") (class "Default")
      (node (ref "JP18") (pin "4") (pinfunction "4_4") (pintype "passive"))
      (node (ref "JP19") (pin "4") (pinfunction "4_4") (pintype "passive"))
      (node (ref "U2") (pin "13") (pinfunction "BUSY_13") (pintype "passive"))
    )
    (net (code "225") (name "Net-(U2-DOUT)") (class "Default")
      (node (ref "JP18") (pin "5") (pinfunction "5_5") (pintype "passive"))
      (node (ref "JP19") (pin "5") (pinfunction "5_5") (pintype "passive"))
      (node (ref "U2") (pin "12") (pinfunction "DOUT_12") (pintype "passive"))
    )
    (net (code "226") (name "Net-(U2-GND)") (class "Default")
      (node (ref "JP16") (pin "6") (pinfunction "6_6") (pintype "passive"))
      (node (ref "JP17") (pin "6") (pinfunction "6_6") (pintype "passive"))
      (node (ref "U2") (pin "6") (pinfunction "GND_6") (pintype "passive"))
    )
    (net (code "227") (name "Net-(U2-IOVDD)") (class "Default")
      (node (ref "C16") (pin "2") (pinfunction "2_2") (pintype "passive"))
      (node (ref "JP18") (pin "7") (pinfunction "7_7") (pintype "passive"))
      (node (ref "JP19") (pin "7") (pinfunction "7_7") (pintype "passive"))
      (node (ref "U2") (pin "10") (pinfunction "IOVDD_10") (pintype "passive"))
    )
    (net (code "228") (name "Net-(U2-VCC)") (class "Default")
      (node (ref "JP16") (pin "1") (pinfunction "1_1") (pintype "passive"))
      (node (ref "JP17") (pin "1") (pinfunction "1_1") (pintype "passive"))
      (node (ref "U2") (pin "1") (pinfunction "VCC_1") (pintype "passive"))
    )
    (net (code "229") (name "Net-(U2-Vbat)") (class "Default")
      (node (ref "JP16") (pin "7") (pinfunction "7_7") (pintype "passive"))
      (node (ref "JP17") (pin "7") (pinfunction "7_7") (pintype "passive"))
      (node (ref "U2") (pin "7") (pinfunction "Vbat_7") (pintype "passive"))
    )
    (net (code "230") (name "Net-(U2-Vref)") (class "Default")
      (node (ref "C15") (pin "2") (pinfunction "2_2") (pintype "passive"))
      (node (ref "JP18") (pin "8") (pinfunction "8_8") (pintype "passive"))
      (node (ref "JP19") (pin "8") (pinfunction "8_8") (pintype "passive"))
      (node (ref "U2") (pin "9") (pinfunction "Vref_9") (pintype "passive"))
    )
    (net (code "231") (name "Net-(U2-X+)") (class "Default")
      (node (ref "C14") (pin "2") (pinfunction "2_2") (pintype "passive"))
      (node (ref "JP16") (pin "2") (pinfunction "2_2") (pintype "passive"))
      (node (ref "JP17") (pin "2") (pinfunction "2_2") (pintype "passive"))
      (node (ref "U2") (pin "2") (pinfunction "X+_2") (pintype "passive"))
    )
    (net (code "232") (name "Net-(U2-X-)") (class "Default")
      (node (ref "C18") (pin "2") (pinfunction "2_2") (pintype "passive"))
      (node (ref "JP16") (pin "4") (pinfunction "4_4") (pintype "passive"))
      (node (ref "JP17") (pin "4") (pinfunction "4_4") (pintype "passive"))
      (node (ref "U2") (pin "4") (pinfunction "X-_4") (pintype "passive"))
    )
    (net (code "233") (name "Net-(U2-Y+)") (class "Default")
      (node (ref "C13") (pin "2") (pinfunction "2_2") (pintype "passive"))
      (node (ref "JP16") (pin "3") (pinfunction "3_3") (pintype "passive"))
      (node (ref "JP17") (pin "3") (pinfunction "3_3") (pintype "passive"))
      (node (ref "U2") (pin "3") (pinfunction "Y+_3") (pintype "passive"))
    )
    (net (code "234") (name "Net-(U2-Y-)") (class "Default")
      (node (ref "C17") (pin "2") (pinfunction "2_2") (pintype "passive"))
      (node (ref "JP16") (pin "5") (pinfunction "5_5") (pintype "passive"))
      (node (ref "JP17") (pin "5") (pinfunction "5_5") (pintype "passive"))
      (node (ref "U2") (pin "5") (pinfunction "Y-_5") (pintype "passive"))
    )
    (net (code "235") (name "Net-(U2-~{CS})") (class "Default")
      (node (ref "JP18") (pin "2") (pinfunction "2_2") (pintype "passive"))
      (node (ref "JP19") (pin "2") (pinfunction "2_2") (pintype "passive"))
      (node (ref "U2") (pin "15") (pinfunction "~{CS}_15") (pintype "passive"))
    )
    (net (code "236") (name "Net-(U2-~{PENIRQ})") (class "Default")
      (node (ref "JP18") (pin "6") (pinfunction "6_6") (pintype "passive"))
      (node (ref "JP19") (pin "6") (pinfunction "6_6") (pintype "passive"))
      (node (ref "U2") (pin "11") (pinfunction "~{PENIRQ}_11") (pintype "passive"))
    )
    (net (code "237") (name "Net-(U12-ENO)") (class "Default")
      (node (ref "C33") (pin "1") (pinfunction "1_1") (pintype "passive"))
      (node (ref "R5") (pin "1") (pinfunction "1_1") (pintype "passive"))
      (node (ref "U12") (pin "1") (pinfunction "ENO_1") (pintype "passive"))
      (node (ref "U12") (pin "4") (pinfunction "Vcc_4") (pintype "passive"))
    )
  )
)
